# MCU.net
KiCad netlist of a schematic drawn in Altium Designer
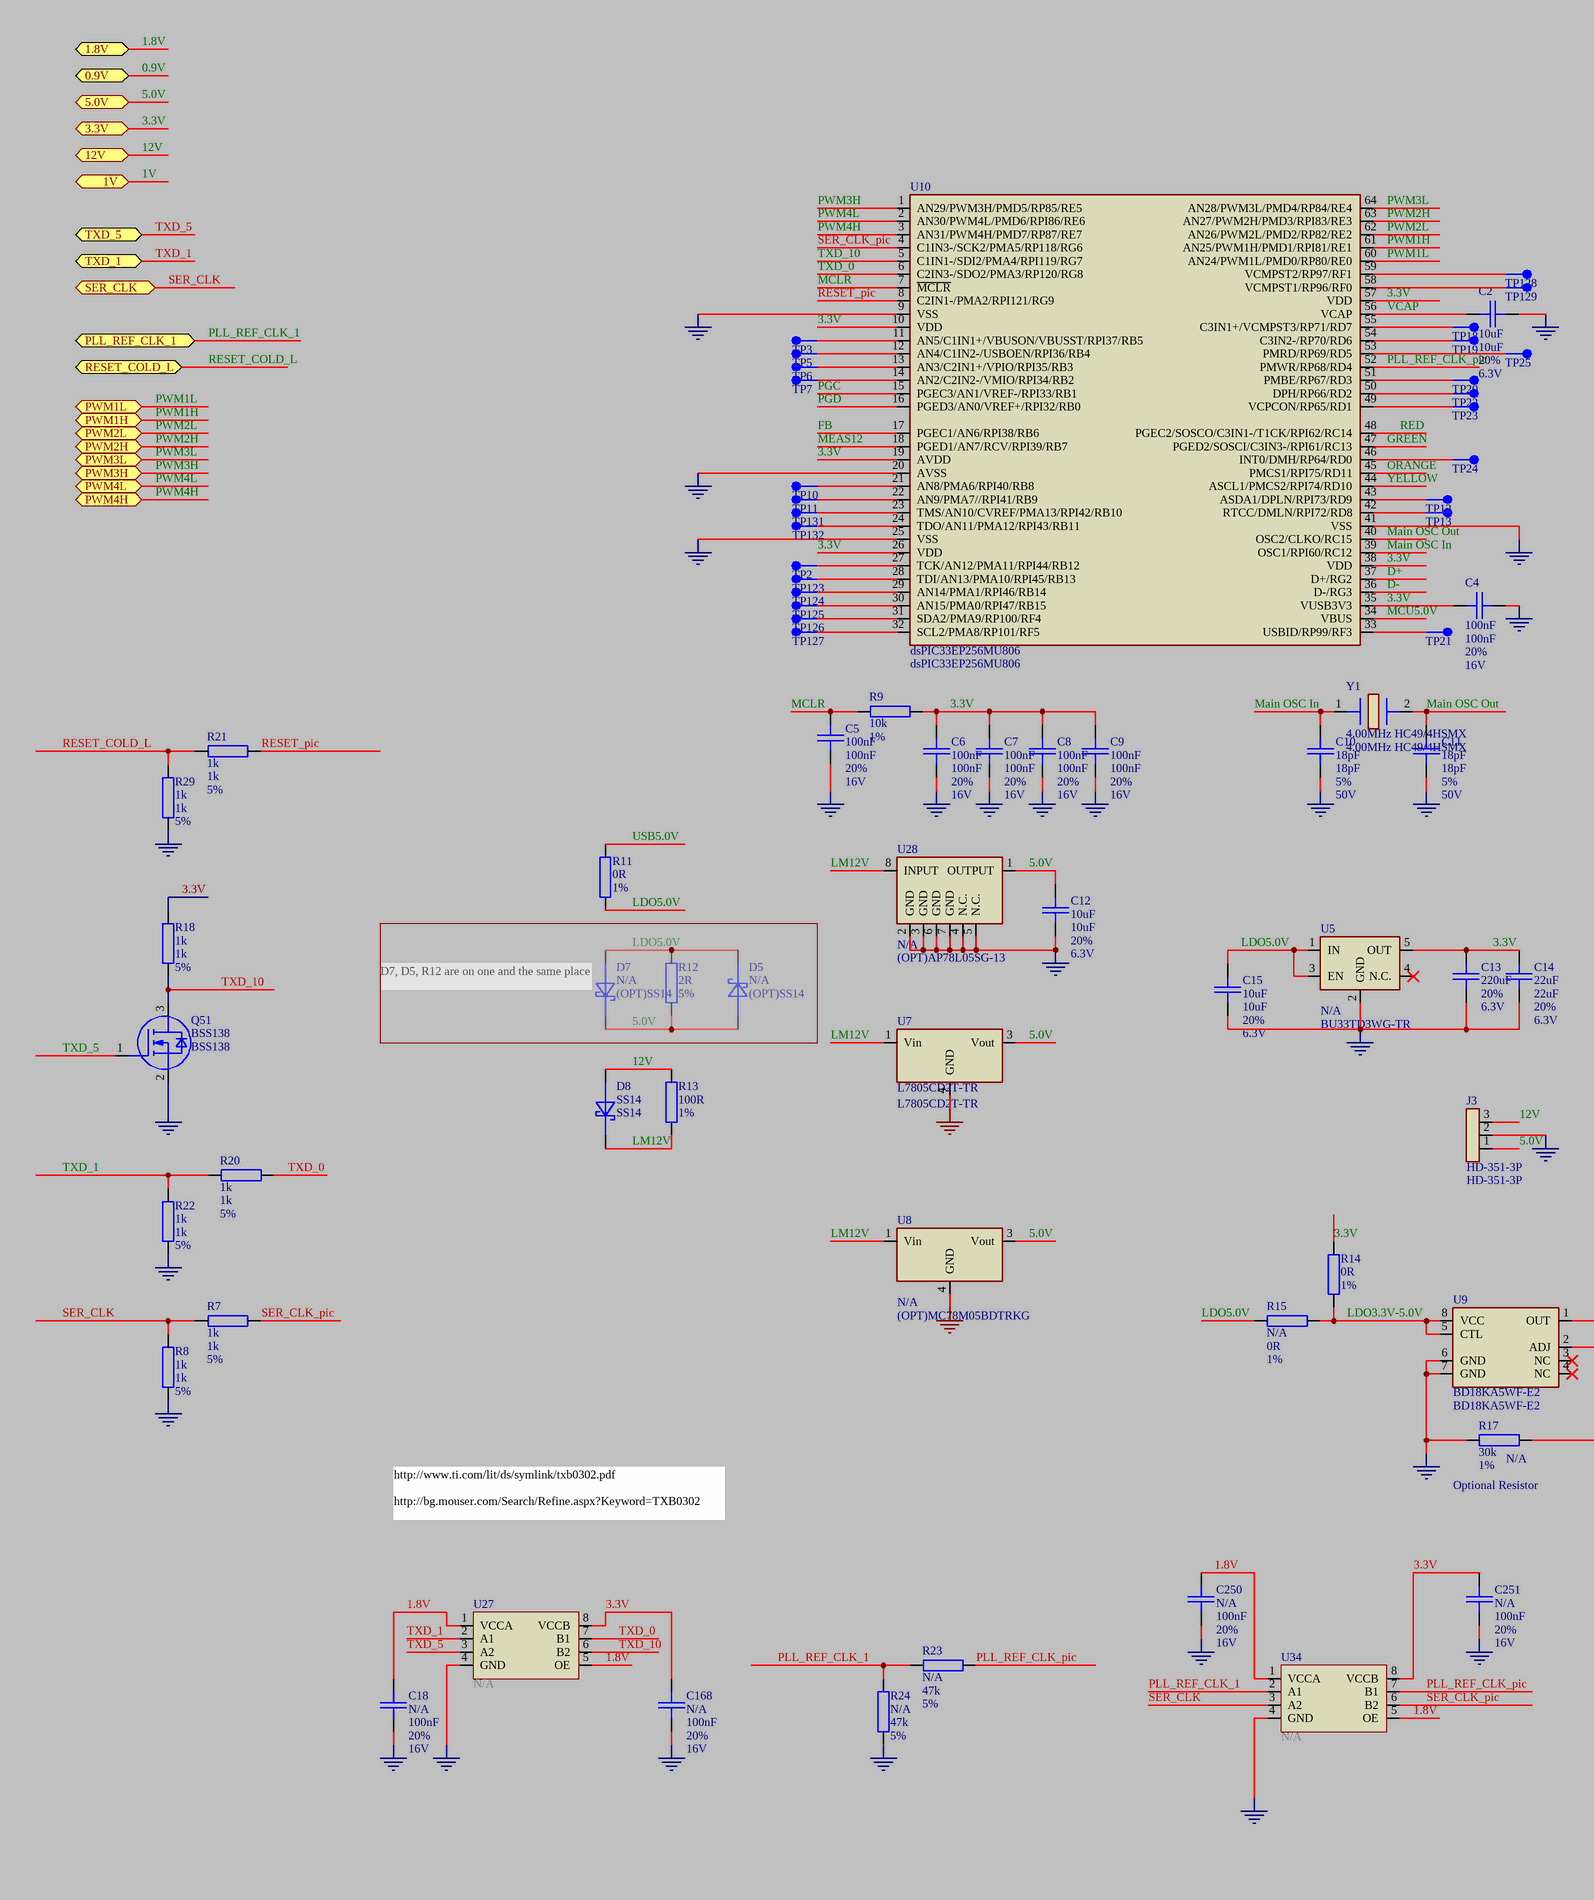
[diagram p0: MCU.SchDoc, left]
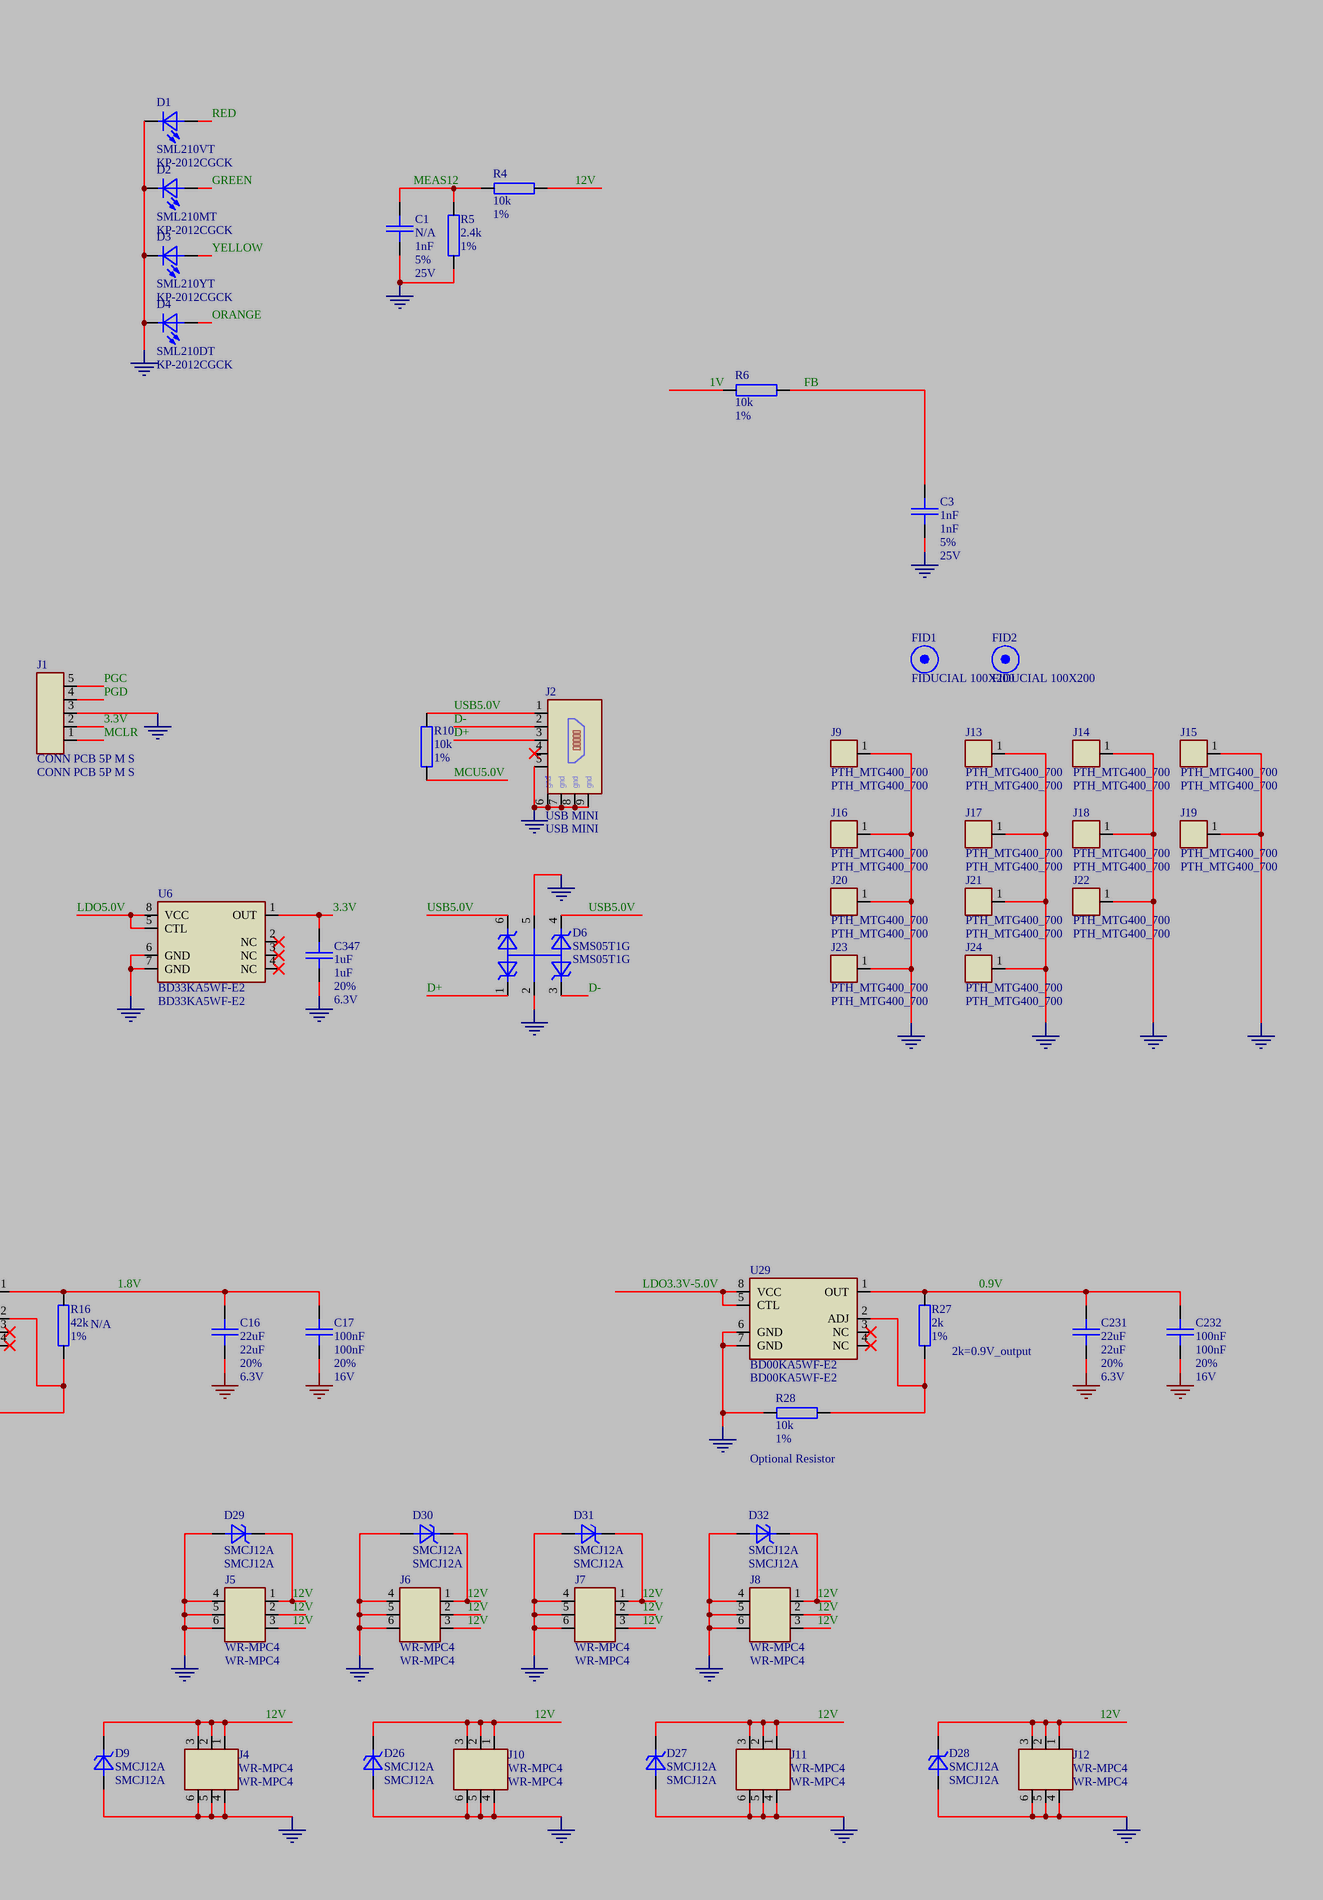
[diagram p1: MCU.SchDoc, right]

(export (version "E")
  (design (tool "Eeschema 10.0.6"))
  (components
    (comp (ref "C1")
      (value "N/A")
      (footprint "SMD_0603_CAPC1608X95N")
      (fields
        (field (name "DB_PART_NUMBER") "CAP000024113")
        (field (name "DB_VALUE") "1nF")
        (field (name "DB_TOLERANCE") "5%")
        (field (name "DB_VOLTAGE") "25V")
        (field (name "DB_MANUFACTURER_PART") "KEMET    C0603C102J3RAC")
      )
      (libsource (lib "") (part "=DB_VALUE_3"))
    )
    (comp (ref "C2")
      (value "10uF")
      (footprint "SMD_0603_CAPC1608X95N")
      (fields
        (field (name "DB_PART_NUMBER") "CAP000043646")
        (field (name "DB_VALUE") "10uF")
        (field (name "DB_TOLERANCE") "20%")
        (field (name "DB_VOLTAGE") "6.3V")
        (field (name "DB_MANUFACTURER_PART") "KEMET    C0603C106M9PAC")
      )
      (libsource (lib "") (part "=DB_VALUE_3"))
    )
    (comp (ref "C3")
      (value "1nF")
      (footprint "SMD_0603_CAPC1608X95N")
      (fields
        (field (name "DB_PART_NUMBER") "CAP000024113")
        (field (name "DB_VALUE") "1nF")
        (field (name "DB_TOLERANCE") "5%")
        (field (name "DB_VOLTAGE") "25V")
        (field (name "DB_MANUFACTURER_PART") "KEMET    C0603C102J3RAC")
      )
      (libsource (lib "") (part "=DB_VALUE_3"))
    )
    (comp (ref "C4")
      (value "100nF")
      (footprint "SMD_0402_CAPC1005X55N")
      (fields
        (field (name "DB_PART_NUMBER") "CAP000022751")
        (field (name "DB_VALUE") "100nF")
        (field (name "DB_TOLERANCE") "20%")
        (field (name "DB_VOLTAGE") "16V")
        (field (name "DB_MANUFACTURER_PART") "KEMET    C0402F104M4RAC")
      )
      (libsource (lib "") (part "=DB_VALUE_3"))
    )
    (comp (ref "C5")
      (value "100nF")
      (footprint "SMD_0402_CAPC1005X55N")
      (fields
        (field (name "DB_PART_NUMBER") "CAP000022751")
        (field (name "DB_VALUE") "100nF")
        (field (name "DB_TOLERANCE") "20%")
        (field (name "DB_VOLTAGE") "16V")
        (field (name "DB_MANUFACTURER_PART") "KEMET    C0402F104M4RAC")
      )
      (libsource (lib "") (part "=DB_VALUE_3"))
    )
    (comp (ref "C6")
      (value "100nF")
      (footprint "SMD_0402_CAPC1005X55N")
      (fields
        (field (name "DB_PART_NUMBER") "CAP000022751")
        (field (name "DB_VALUE") "100nF")
        (field (name "DB_TOLERANCE") "20%")
        (field (name "DB_VOLTAGE") "16V")
        (field (name "DB_MANUFACTURER_PART") "KEMET    C0402F104M4RAC")
      )
      (libsource (lib "") (part "=DB_VALUE_3"))
    )
    (comp (ref "C7")
      (value "100nF")
      (footprint "SMD_0402_CAPC1005X55N")
      (fields
        (field (name "DB_PART_NUMBER") "CAP000022751")
        (field (name "DB_VALUE") "100nF")
        (field (name "DB_TOLERANCE") "20%")
        (field (name "DB_VOLTAGE") "16V")
        (field (name "DB_MANUFACTURER_PART") "KEMET    C0402F104M4RAC")
      )
      (libsource (lib "") (part "=DB_VALUE_3"))
    )
    (comp (ref "C8")
      (value "100nF")
      (footprint "SMD_0402_CAPC1005X55N")
      (fields
        (field (name "DB_PART_NUMBER") "CAP000022751")
        (field (name "DB_VALUE") "100nF")
        (field (name "DB_TOLERANCE") "20%")
        (field (name "DB_VOLTAGE") "16V")
        (field (name "DB_MANUFACTURER_PART") "KEMET    C0402F104M4RAC")
      )
      (libsource (lib "") (part "=DB_VALUE_3"))
    )
    (comp (ref "C9")
      (value "100nF")
      (footprint "SMD_0402_CAPC1005X55N")
      (fields
        (field (name "DB_PART_NUMBER") "CAP000022751")
        (field (name "DB_VALUE") "100nF")
        (field (name "DB_TOLERANCE") "20%")
        (field (name "DB_VOLTAGE") "16V")
        (field (name "DB_MANUFACTURER_PART") "KEMET    C0402F104M4RAC")
      )
      (libsource (lib "") (part "=DB_VALUE_3"))
    )
    (comp (ref "C10")
      (value "18pF")
      (footprint "SMD_0603_CAPC1608X95N")
      (fields
        (field (name "DB_PART_NUMBER") "CAP000031922")
        (field (name "DB_VALUE") "18pF")
        (field (name "DB_TOLERANCE") "5%")
        (field (name "DB_VOLTAGE") "50V")
        (field (name "DB_MANUFACTURER_PART") "KEMET    C0603C180J5GAC")
      )
      (libsource (lib "") (part "=DB_VALUE_3"))
    )
    (comp (ref "C11")
      (value "18pF")
      (footprint "SMD_0603_CAPC1608X95N")
      (fields
        (field (name "DB_PART_NUMBER") "CAP000031922")
        (field (name "DB_VALUE") "18pF")
        (field (name "DB_TOLERANCE") "5%")
        (field (name "DB_VOLTAGE") "50V")
        (field (name "DB_MANUFACTURER_PART") "KEMET    C0603C180J5GAC")
      )
      (libsource (lib "") (part "=DB_VALUE_3"))
    )
    (comp (ref "C12")
      (value "10uF")
      (footprint "SMD_0603_CAPC1608X95N")
      (fields
        (field (name "DB_PART_NUMBER") "CAP000043646")
        (field (name "DB_VALUE") "10uF")
        (field (name "DB_TOLERANCE") "20%")
        (field (name "DB_VOLTAGE") "6.3V")
        (field (name "DB_MANUFACTURER_PART") "KEMET    C0603C106M9PAC")
      )
      (libsource (lib "") (part "=DB_VALUE_3"))
    )
    (comp (ref "C13")
      (value "220uF")
      (footprint "SMD_1210_CAPC3225X279N")
      (fields
        (field (name "DB_PART_NUMBER") "CAP000047355")
        (field (name "DB_VALUE") "220uF")
        (field (name "DB_TOLERANCE") "20%")
        (field (name "DB_VOLTAGE") "6.3V")
        (field (name "DB_MANUFACTURER_PART") "SAMSUNG    CL32A227MQVNNNE")
        (field (name "DB_APPROVED_BY") "VSN")
      )
      (libsource (lib "") (part "=DB_VALUE_3"))
    )
    (comp (ref "C14")
      (value "22uF")
      (footprint "SMD_0805_CAPC2012X145N")
      (fields
        (field (name "DB_PART_NUMBER") "CAP000043686")
        (field (name "DB_VALUE") "22uF")
        (field (name "DB_TOLERANCE") "20%")
        (field (name "DB_VOLTAGE") "6.3V")
        (field (name "DB_MANUFACTURER_PART") "KEMET    C0805C226M9PAC")
      )
      (libsource (lib "") (part "=DB_VALUE_3"))
    )
    (comp (ref "C15")
      (value "10uF")
      (footprint "SMD_0603_CAPC1608X95N")
      (fields
        (field (name "DB_PART_NUMBER") "CAP000043646")
        (field (name "DB_VALUE") "10uF")
        (field (name "DB_TOLERANCE") "20%")
        (field (name "DB_VOLTAGE") "6.3V")
        (field (name "DB_MANUFACTURER_PART") "KEMET    C0603C106M9PAC")
      )
      (libsource (lib "") (part "=DB_VALUE_3"))
    )
    (comp (ref "C16")
      (value "22uF")
      (footprint "SMD_0805_CAPC2012X145N")
      (fields
        (field (name "DB_PART_NUMBER") "CAP000043686")
        (field (name "DB_VALUE") "22uF")
        (field (name "DB_TOLERANCE") "20%")
        (field (name "DB_VOLTAGE") "6.3V")
        (field (name "DB_MANUFACTURER_PART") "KEMET    C0805C226M9PAC")
      )
      (libsource (lib "") (part "=DB_VALUE_3"))
    )
    (comp (ref "C17")
      (value "100nF")
      (footprint "SMD_0402_CAPC1005X55N")
      (fields
        (field (name "DB_PART_NUMBER") "CAP000022751")
        (field (name "DB_VALUE") "100nF")
        (field (name "DB_TOLERANCE") "20%")
        (field (name "DB_VOLTAGE") "16V")
        (field (name "DB_MANUFACTURER_PART") "KEMET    C0402F104M4RAC")
      )
      (libsource (lib "") (part "=DB_VALUE_3"))
    )
    (comp (ref "C18")
      (value "N/A")
      (footprint "SMD_0402_CAPC1005X55N")
      (fields
        (field (name "DB_PART_NUMBER") "CAP000022751")
        (field (name "DB_VALUE") "100nF")
        (field (name "DB_TOLERANCE") "20%")
        (field (name "DB_VOLTAGE") "16V")
        (field (name "DB_MANUFACTURER_PART") "KEMET    C0402F104M4RAC")
      )
      (libsource (lib "") (part "=DB_VALUE_3"))
    )
    (comp (ref "C168")
      (value "N/A")
      (footprint "SMD_0402_CAPC1005X55N")
      (fields
        (field (name "DB_PART_NUMBER") "CAP000022751")
        (field (name "DB_VALUE") "100nF")
        (field (name "DB_TOLERANCE") "20%")
        (field (name "DB_VOLTAGE") "16V")
        (field (name "DB_MANUFACTURER_PART") "KEMET    C0402F104M4RAC")
      )
      (libsource (lib "") (part "=DB_VALUE_3"))
    )
    (comp (ref "C231")
      (value "22uF")
      (footprint "SMD_0805_CAPC2012X145N")
      (fields
        (field (name "DB_PART_NUMBER") "CAP000043686")
        (field (name "DB_VALUE") "22uF")
        (field (name "DB_TOLERANCE") "20%")
        (field (name "DB_VOLTAGE") "6.3V")
        (field (name "DB_MANUFACTURER_PART") "KEMET    C0805C226M9PAC")
      )
      (libsource (lib "") (part "=DB_VALUE_3"))
    )
    (comp (ref "C232")
      (value "100nF")
      (footprint "SMD_0402_CAPC1005X55N")
      (fields
        (field (name "DB_PART_NUMBER") "CAP000022751")
        (field (name "DB_VALUE") "100nF")
        (field (name "DB_TOLERANCE") "20%")
        (field (name "DB_VOLTAGE") "16V")
        (field (name "DB_MANUFACTURER_PART") "KEMET    C0402F104M4RAC")
      )
      (libsource (lib "") (part "=DB_VALUE_3"))
    )
    (comp (ref "C250")
      (value "N/A")
      (footprint "SMD_0402_CAPC1005X55N")
      (fields
        (field (name "DB_PART_NUMBER") "CAP000022751")
        (field (name "DB_VALUE") "100nF")
        (field (name "DB_TOLERANCE") "20%")
        (field (name "DB_VOLTAGE") "16V")
        (field (name "DB_MANUFACTURER_PART") "KEMET    C0402F104M4RAC")
      )
      (libsource (lib "") (part "=DB_VALUE_3"))
    )
    (comp (ref "C251")
      (value "N/A")
      (footprint "SMD_0402_CAPC1005X55N")
      (fields
        (field (name "DB_PART_NUMBER") "CAP000022751")
        (field (name "DB_VALUE") "100nF")
        (field (name "DB_TOLERANCE") "20%")
        (field (name "DB_VOLTAGE") "16V")
        (field (name "DB_MANUFACTURER_PART") "KEMET    C0402F104M4RAC")
      )
      (libsource (lib "") (part "=DB_VALUE_3"))
    )
    (comp (ref "C347")
      (value "1uF")
      (footprint "SMD_0603_CAPC1608X95N")
      (fields
        (field (name "DB_PART_NUMBER") "CAP000043344")
        (field (name "DB_VALUE") "1uF")
        (field (name "DB_TOLERANCE") "20%")
        (field (name "DB_VOLTAGE") "6.3V")
        (field (name "DB_MANUFACTURER_PART") "KEMET    C0603C105M9PAC")
      )
      (libsource (lib "") (part "=DB_VALUE_3"))
    )
    (comp (ref "D1")
      (value "SML210VT")
      (footprint "SMD_0805_LED2012X100N")
      (fields
        (field (name "DB_PART_NUMBER") "OPT000000096")
        (field (name "DB_VALUE") "KP-2012CGCK")
        (field (name "DB_MANUFACTURER_PART") "KINGBRIGHT       KP-2012CGCK")
        (field (name "DB_APPROVED_BY") "VSN")
      )
      (libsource (lib "Database_Libs1") (part "LED"))
    )
    (comp (ref "D2")
      (value "SML210MT")
      (footprint "SMD_0805_LED2012X100N")
      (fields
        (field (name "DB_PART_NUMBER") "OPT000000096")
        (field (name "DB_VALUE") "KP-2012CGCK")
        (field (name "DB_MANUFACTURER_PART") "KINGBRIGHT       KP-2012CGCK")
        (field (name "DB_APPROVED_BY") "VSN")
      )
      (libsource (lib "Database_Libs1") (part "LED"))
    )
    (comp (ref "D3")
      (value "SML210YT")
      (footprint "SMD_0805_LED2012X100N")
      (fields
        (field (name "DB_PART_NUMBER") "OPT000000096")
        (field (name "DB_VALUE") "KP-2012CGCK")
        (field (name "DB_MANUFACTURER_PART") "KINGBRIGHT       KP-2012CGCK")
        (field (name "DB_APPROVED_BY") "VSN")
      )
      (libsource (lib "Database_Libs1") (part "LED"))
    )
    (comp (ref "D4")
      (value "SML210DT")
      (footprint "SMD_0805_LED2012X100N")
      (fields
        (field (name "DB_PART_NUMBER") "OPT000000096")
        (field (name "DB_VALUE") "KP-2012CGCK")
        (field (name "DB_MANUFACTURER_PART") "KINGBRIGHT       KP-2012CGCK")
        (field (name "DB_APPROVED_BY") "VSN")
      )
      (libsource (lib "Database_Libs1") (part "LED"))
    )
    (comp (ref "D5")
      (value "N/A")
      (footprint "SMD_DO214AC_SMA")
      (fields
        (field (name "DB_PART_NUMBER") "DDE000000580")
        (field (name "DB_VALUE") "(OPT)SS14")
        (field (name "DB_MANUFACTURER_PART") "Diodes        B140")
      )
      (libsource (lib "") (part "=DB_VALUE_13"))
    )
    (comp (ref "D6")
      (value "SMS05T1G")
      (footprint "SMD_SOT457_SOT95P275X110-6N")
      (fields
        (field (name "DB_PART_NUMBER") "DDE000002846")
        (field (name "DB_VALUE") "SMS05T1G")
        (field (name "DB_MANUFACTURER_PART") "ON SEMICONDUCTOR        SMS05T1G")
        (field (name "DB_APPROVED_BY") "VSN")
      )
      (libsource (lib "") (part "=DB_VALUE_15"))
    )
    (comp (ref "D7")
      (value "N/A")
      (footprint "SMD_DO214AC_SMA")
      (fields
        (field (name "DB_PART_NUMBER") "DDE000000580")
        (field (name "DB_VALUE") "(OPT)SS14")
        (field (name "DB_MANUFACTURER_PART") "Diodes        B140")
      )
      (libsource (lib "") (part "=DB_VALUE_13"))
    )
    (comp (ref "D8")
      (value "SS14")
      (footprint "SMD_DO214AC_SMA")
      (fields
        (field (name "DB_PART_NUMBER") "DDE000000580")
        (field (name "DB_VALUE") "SS14")
        (field (name "DB_MANUFACTURER_PART") "Diodes        B140")
      )
      (libsource (lib "") (part "=DB_VALUE_13"))
    )
    (comp (ref "D9")
      (value "SMCJ12A")
      (footprint "SMD_DO214AC_SMC")
      (fields
        (field (name "DB_PART_NUMBER") "DDE000001725")
        (field (name "DB_VALUE") "SMCJ12A")
        (field (name "DB_MANUFACTURER_PART") "Diodes        SMCJ12A")
      )
      (libsource (lib "") (part "=DB_VALUE_9"))
    )
    (comp (ref "D26")
      (value "SMCJ12A")
      (footprint "SMD_DO214AC_SMC")
      (fields
        (field (name "DB_PART_NUMBER") "DDE000001725")
        (field (name "DB_VALUE") "SMCJ12A")
        (field (name "DB_MANUFACTURER_PART") "Diodes        SMCJ12A")
      )
      (libsource (lib "") (part "=DB_VALUE_9"))
    )
    (comp (ref "D27")
      (value "SMCJ12A")
      (footprint "SMD_DO214AC_SMC")
      (fields
        (field (name "DB_PART_NUMBER") "DDE000001725")
        (field (name "DB_VALUE") "SMCJ12A")
        (field (name "DB_MANUFACTURER_PART") "Diodes        SMCJ12A")
      )
      (libsource (lib "") (part "=DB_VALUE_9"))
    )
    (comp (ref "D28")
      (value "SMCJ12A")
      (footprint "SMD_DO214AC_SMC")
      (fields
        (field (name "DB_PART_NUMBER") "DDE000001725")
        (field (name "DB_VALUE") "SMCJ12A")
        (field (name "DB_MANUFACTURER_PART") "Diodes        SMCJ12A")
      )
      (libsource (lib "") (part "=DB_VALUE_9"))
    )
    (comp (ref "D29")
      (value "SMCJ12A")
      (footprint "SMD_DO214AC_SMC")
      (fields
        (field (name "DB_PART_NUMBER") "DDE000001725")
        (field (name "DB_VALUE") "SMCJ12A")
        (field (name "DB_MANUFACTURER_PART") "Diodes        SMCJ12A")
      )
      (libsource (lib "") (part "=DB_VALUE_9"))
    )
    (comp (ref "D30")
      (value "SMCJ12A")
      (footprint "SMD_DO214AC_SMC")
      (fields
        (field (name "DB_PART_NUMBER") "DDE000001725")
        (field (name "DB_VALUE") "SMCJ12A")
        (field (name "DB_MANUFACTURER_PART") "Diodes        SMCJ12A")
      )
      (libsource (lib "") (part "=DB_VALUE_9"))
    )
    (comp (ref "D31")
      (value "SMCJ12A")
      (footprint "SMD_DO214AC_SMC")
      (fields
        (field (name "DB_PART_NUMBER") "DDE000001725")
        (field (name "DB_VALUE") "SMCJ12A")
        (field (name "DB_MANUFACTURER_PART") "Diodes        SMCJ12A")
      )
      (libsource (lib "") (part "=DB_VALUE_9"))
    )
    (comp (ref "D32")
      (value "SMCJ12A")
      (footprint "SMD_DO214AC_SMC")
      (fields
        (field (name "DB_PART_NUMBER") "DDE000001725")
        (field (name "DB_VALUE") "SMCJ12A")
        (field (name "DB_MANUFACTURER_PART") "Diodes        SMCJ12A")
      )
      (libsource (lib "") (part "=DB_VALUE_9"))
    )
    (comp (ref "FID1")
      (value "FIDUCIAL 100X200")
      (footprint "FID100X200")
      (fields
        (field (name "DB_PART_NUMBER") "FID000000001")
        (field (name "DB_MANUFACTURER_PART") "ISHIDDEN=T")
        (field (name "DB_APPROVED_BY") "ISHIDDEN=T")
      )
      (libsource (lib "") (part "=DB_VALUE_8"))
    )
    (comp (ref "FID2")
      (value "FIDUCIAL 100X200")
      (footprint "FID100X200")
      (fields
        (field (name "DB_PART_NUMBER") "FID000000001")
        (field (name "DB_MANUFACTURER_PART") "ISHIDDEN=T")
        (field (name "DB_APPROVED_BY") "ISHIDDEN=T")
      )
      (libsource (lib "") (part "=DB_VALUE_8"))
    )
    (comp (ref "J1")
      (value "CONN PCB 5P M S")
      (footprint "PTH_HDRV05W64P254_1X05")
      (fields
        (field (name "DB_PART_NUMBER") "CON000000006")
        (field (name "DB_VALUE") "CONN PCB 5P M S")
        (field (name "DB_MANUFACTURER_PART") "W+P        143-12-005-00")
        (field (name "DB_APPROVED_BY") "VSN")
      )
      (libsource (lib "") (part "=DB_VALUE_18"))
    )
    (comp (ref "J2")
      (value "USB MINI")
      (footprint "SMD_CON-CVILUX-CU04-SCM15B0")
      (fields
        (field (name "DB_PART_NUMBER") "CON000000048")
        (field (name "DB_VALUE") "USB MINI")
        (field (name "DB_MANUFACTURER_PART") "CVILUX       CU04-SCM15B0-R0-LF")
        (field (name "DB_APPROVED_BY") "VSN")
      )
      (libsource (lib "") (part "=DB_VALUE_16"))
    )
    (comp (ref "J3")
      (value "HD-351-3P")
      (footprint "PTH_CON_HD-351-3P")
      (fields
        (field (name "DB_PART_NUMBER") "CON000000272")
        (field (name "DB_VALUE") "HD-351-3P")
        (field (name "DB_MANUFACTURER_PART") "HOW DER      HD-351-3P")
        (field (name "DB_APPROVED_BY") "VSN")
      )
      (libsource (lib "") (part "=DB_VALUE_19"))
    )
    (comp (ref "J4")
      (value "WR-MPC4")
      (footprint "PTH_CON_WR-MRC4-6P_S")
      (fields
        (field (name "DB_PART_NUMBER") "CON000000279")
        (field (name "DB_VALUE") "WR-MPC4")
        (field (name "DB_MANUFACTURER_PART") "WE        	649 006 211 22")
        (field (name "DB_APPROVED_BY") "VSN")
      )
      (libsource (lib "") (part "=DB_VALUE_6"))
    )
    (comp (ref "J5")
      (value "WR-MPC4")
      (footprint "PTH_CON_WR-MRC4-6P_S")
      (fields
        (field (name "DB_PART_NUMBER") "CON000000279")
        (field (name "DB_VALUE") "WR-MPC4")
        (field (name "DB_MANUFACTURER_PART") "WE        	649 006 211 22")
        (field (name "DB_APPROVED_BY") "VSN")
      )
      (libsource (lib "") (part "=DB_VALUE_6"))
    )
    (comp (ref "J6")
      (value "WR-MPC4")
      (footprint "PTH_CON_WR-MRC4-6P_S")
      (fields
        (field (name "DB_PART_NUMBER") "CON000000279")
        (field (name "DB_VALUE") "WR-MPC4")
        (field (name "DB_MANUFACTURER_PART") "WE        	649 006 211 22")
        (field (name "DB_APPROVED_BY") "VSN")
      )
      (libsource (lib "") (part "=DB_VALUE_6"))
    )
    (comp (ref "J7")
      (value "WR-MPC4")
      (footprint "PTH_CON_WR-MRC4-6P_S")
      (fields
        (field (name "DB_PART_NUMBER") "CON000000279")
        (field (name "DB_VALUE") "WR-MPC4")
        (field (name "DB_MANUFACTURER_PART") "WE        	649 006 211 22")
        (field (name "DB_APPROVED_BY") "VSN")
      )
      (libsource (lib "") (part "=DB_VALUE_6"))
    )
    (comp (ref "J8")
      (value "WR-MPC4")
      (footprint "PTH_CON_WR-MRC4-6P_S")
      (fields
        (field (name "DB_PART_NUMBER") "CON000000279")
        (field (name "DB_VALUE") "WR-MPC4")
        (field (name "DB_MANUFACTURER_PART") "WE        	649 006 211 22")
        (field (name "DB_APPROVED_BY") "VSN")
      )
      (libsource (lib "") (part "=DB_VALUE_6"))
    )
    (comp (ref "J9")
      (value "PTH_MTG400_700")
      (footprint "PTH_MTG400_700")
      (fields
        (field (name "DB_PART_NUMBER") "MTH000000030")
        (field (name "DB_VALUE") "PTH_MTG400_700")
        (field (name "DB_APPROVED_BY") "VSN")
      )
      (libsource (lib "") (part "=DB_VALUE_4"))
    )
    (comp (ref "J10")
      (value "WR-MPC4")
      (footprint "PTH_CON_WR-MRC4-6P_S")
      (fields
        (field (name "DB_PART_NUMBER") "CON000000279")
        (field (name "DB_VALUE") "WR-MPC4")
        (field (name "DB_MANUFACTURER_PART") "WE        	649 006 211 22")
        (field (name "DB_APPROVED_BY") "VSN")
      )
      (libsource (lib "") (part "=DB_VALUE_6"))
    )
    (comp (ref "J11")
      (value "WR-MPC4")
      (footprint "PTH_CON_WR-MRC4-6P_S")
      (fields
        (field (name "DB_PART_NUMBER") "CON000000279")
        (field (name "DB_VALUE") "WR-MPC4")
        (field (name "DB_MANUFACTURER_PART") "WE        	649 006 211 22")
        (field (name "DB_APPROVED_BY") "VSN")
      )
      (libsource (lib "") (part "=DB_VALUE_6"))
    )
    (comp (ref "J12")
      (value "WR-MPC4")
      (footprint "PTH_CON_WR-MRC4-6P_S")
      (fields
        (field (name "DB_PART_NUMBER") "CON000000279")
        (field (name "DB_VALUE") "WR-MPC4")
        (field (name "DB_MANUFACTURER_PART") "WE        	649 006 211 22")
        (field (name "DB_APPROVED_BY") "VSN")
      )
      (libsource (lib "") (part "=DB_VALUE_6"))
    )
    (comp (ref "J13")
      (value "PTH_MTG400_700")
      (footprint "PTH_MTG400_700")
      (fields
        (field (name "DB_PART_NUMBER") "MTH000000030")
        (field (name "DB_VALUE") "PTH_MTG400_700")
        (field (name "DB_APPROVED_BY") "VSN")
      )
      (libsource (lib "") (part "=DB_VALUE_4"))
    )
    (comp (ref "J14")
      (value "PTH_MTG400_700")
      (footprint "PTH_MTG400_700")
      (fields
        (field (name "DB_PART_NUMBER") "MTH000000030")
        (field (name "DB_VALUE") "PTH_MTG400_700")
        (field (name "DB_APPROVED_BY") "VSN")
      )
      (libsource (lib "") (part "=DB_VALUE_4"))
    )
    (comp (ref "J15")
      (value "PTH_MTG400_700")
      (footprint "PTH_MTG400_700")
      (fields
        (field (name "DB_PART_NUMBER") "MTH000000030")
        (field (name "DB_VALUE") "PTH_MTG400_700")
        (field (name "DB_APPROVED_BY") "VSN")
      )
      (libsource (lib "") (part "=DB_VALUE_4"))
    )
    (comp (ref "J16")
      (value "PTH_MTG400_700")
      (footprint "PTH_MTG400_700")
      (fields
        (field (name "DB_PART_NUMBER") "MTH000000030")
        (field (name "DB_VALUE") "PTH_MTG400_700")
        (field (name "DB_APPROVED_BY") "VSN")
      )
      (libsource (lib "") (part "=DB_VALUE_4"))
    )
    (comp (ref "J17")
      (value "PTH_MTG400_700")
      (footprint "PTH_MTG400_700")
      (fields
        (field (name "DB_PART_NUMBER") "MTH000000030")
        (field (name "DB_VALUE") "PTH_MTG400_700")
        (field (name "DB_APPROVED_BY") "VSN")
      )
      (libsource (lib "") (part "=DB_VALUE_4"))
    )
    (comp (ref "J18")
      (value "PTH_MTG400_700")
      (footprint "PTH_MTG400_700")
      (fields
        (field (name "DB_PART_NUMBER") "MTH000000030")
        (field (name "DB_VALUE") "PTH_MTG400_700")
        (field (name "DB_APPROVED_BY") "VSN")
      )
      (libsource (lib "") (part "=DB_VALUE_4"))
    )
    (comp (ref "J19")
      (value "PTH_MTG400_700")
      (footprint "PTH_MTG400_700")
      (fields
        (field (name "DB_PART_NUMBER") "MTH000000030")
        (field (name "DB_VALUE") "PTH_MTG400_700")
        (field (name "DB_APPROVED_BY") "VSN")
      )
      (libsource (lib "") (part "=DB_VALUE_4"))
    )
    (comp (ref "J20")
      (value "PTH_MTG400_700")
      (footprint "PTH_MTG400_700")
      (fields
        (field (name "DB_PART_NUMBER") "MTH000000030")
        (field (name "DB_VALUE") "PTH_MTG400_700")
        (field (name "DB_APPROVED_BY") "VSN")
      )
      (libsource (lib "") (part "=DB_VALUE_4"))
    )
    (comp (ref "J21")
      (value "PTH_MTG400_700")
      (footprint "PTH_MTG400_700")
      (fields
        (field (name "DB_PART_NUMBER") "MTH000000030")
        (field (name "DB_VALUE") "PTH_MTG400_700")
        (field (name "DB_APPROVED_BY") "VSN")
      )
      (libsource (lib "") (part "=DB_VALUE_4"))
    )
    (comp (ref "J22")
      (value "PTH_MTG400_700")
      (footprint "PTH_MTG400_700")
      (fields
        (field (name "DB_PART_NUMBER") "MTH000000030")
        (field (name "DB_VALUE") "PTH_MTG400_700")
        (field (name "DB_APPROVED_BY") "VSN")
      )
      (libsource (lib "") (part "=DB_VALUE_4"))
    )
    (comp (ref "J23")
      (value "PTH_MTG400_700")
      (footprint "PTH_MTG400_700")
      (fields
        (field (name "DB_PART_NUMBER") "MTH000000030")
        (field (name "DB_VALUE") "PTH_MTG400_700")
        (field (name "DB_APPROVED_BY") "VSN")
      )
      (libsource (lib "") (part "=DB_VALUE_4"))
    )
    (comp (ref "J24")
      (value "PTH_MTG400_700")
      (footprint "PTH_MTG400_700")
      (fields
        (field (name "DB_PART_NUMBER") "MTH000000030")
        (field (name "DB_VALUE") "PTH_MTG400_700")
        (field (name "DB_APPROVED_BY") "VSN")
      )
      (libsource (lib "") (part "=DB_VALUE_4"))
    )
    (comp (ref "Q51")
      (value "BSS138")
      (footprint "SMD_SOT23_SOT95P240X112-3N")
      (fields
        (field (name "DB_PART_NUMBER") "TRA000001460")
        (field (name "DB_VALUE") "BSS138")
        (field (name "DB_MANUFACTURER_PART") "FAIRCHILD        BSS138LT1G")
        (field (name "DB_APPROVED_BY") "VSN")
      )
      (libsource (lib "") (part "=DB_VALUE_11"))
    )
    (comp (ref "R4")
      (value "N/A")
      (footprint "SMD_0603_RESC1608X55N")
      (fields
        (field (name "DB_PART_NUMBER") "RES000008663")
        (field (name "DB_VALUE") "10k")
        (field (name "DB_TOLERANCE") "1%")
        (field (name "DB_MANUFACTURER_PART") "YAGEO    RC0603FR-0710KL")
        (field (name "DB_APPROVED_BY") "VSN")
      )
      (libsource (lib "") (part "=DB_VALUE_2"))
    )
    (comp (ref "R5")
      (value "N/A")
      (footprint "SMD_0603_RESC1608X55N")
      (fields
        (field (name "DB_PART_NUMBER") "RES000006261")
        (field (name "DB_VALUE") "2.4k")
        (field (name "DB_TOLERANCE") "1%")
        (field (name "DB_MANUFACTURER_PART") "YAGEO    RC0603FR-072K4")
      )
      (libsource (lib "") (part "=DB_VALUE_2"))
    )
    (comp (ref "R6")
      (value "10k")
      (footprint "SMD_0603_RESC1608X55N")
      (fields
        (field (name "DB_PART_NUMBER") "RES000008663")
        (field (name "DB_VALUE") "10k")
        (field (name "DB_TOLERANCE") "1%")
        (field (name "DB_MANUFACTURER_PART") "YAGEO    RC0603FR-0710KL")
        (field (name "DB_APPROVED_BY") "VSN")
      )
      (libsource (lib "") (part "=DB_VALUE_2"))
    )
    (comp (ref "R7")
      (value "1k")
      (footprint "SMD_0603_RESC1608X55N")
      (fields
        (field (name "DB_PART_NUMBER") "RES000006462")
        (field (name "DB_VALUE") "1k")
        (field (name "DB_TOLERANCE") "5%")
        (field (name "DB_MANUFACTURER_PART") "YAGEO    RC0603JR-0747K")
      )
      (libsource (lib "") (part "=DB_VALUE_2"))
    )
    (comp (ref "R8")
      (value "1k")
      (footprint "SMD_0603_RESC1608X55N")
      (fields
        (field (name "DB_PART_NUMBER") "RES000006462")
        (field (name "DB_VALUE") "1k")
        (field (name "DB_TOLERANCE") "5%")
        (field (name "DB_MANUFACTURER_PART") "YAGEO    RC0603JR-0747K")
      )
      (libsource (lib "") (part "=DB_VALUE_2"))
    )
    (comp (ref "R9")
      (value "10k")
      (footprint "SMD_0603_RESC1608X55N")
      (fields
        (field (name "DB_PART_NUMBER") "RES000008663")
        (field (name "DB_VALUE") "10k")
        (field (name "DB_TOLERANCE") "1%")
        (field (name "DB_MANUFACTURER_PART") "YAGEO    RC0603FR-0710KL")
        (field (name "DB_APPROVED_BY") "VSN")
      )
      (libsource (lib "") (part "=DB_VALUE_2"))
    )
    (comp (ref "R10")
      (value "10k")
      (footprint "SMD_0603_RESC1608X55N")
      (fields
        (field (name "DB_PART_NUMBER") "RES000008663")
        (field (name "DB_VALUE") "10k")
        (field (name "DB_TOLERANCE") "1%")
        (field (name "DB_MANUFACTURER_PART") "YAGEO    RC0603FR-0710KL")
        (field (name "DB_APPROVED_BY") "VSN")
      )
      (libsource (lib "") (part "=DB_VALUE_2"))
    )
    (comp (ref "R11")
      (value "0R")
      (footprint "SMD_0603_RESC1608X55N")
      (fields
        (field (name "DB_PART_NUMBER") "RES000008926")
        (field (name "DB_VALUE") "0R")
        (field (name "DB_TOLERANCE") "1%")
        (field (name "DB_MANUFACTURER_PART") "YAGEO    AC0603FR-070RL")
        (field (name "DB_APPROVED_BY") "VSN")
      )
      (libsource (lib "") (part "=DB_VALUE_2"))
    )
    (comp (ref "R12")
      (value "2R")
      (footprint "SMD_1206_RESC3216X65N")
      (fields
        (field (name "DB_PART_NUMBER") "RES000007051")
        (field (name "DB_VALUE") "2R")
        (field (name "DB_TOLERANCE") "5%")
        (field (name "DB_MANUFACTURER_PART") "YAGEO    RC1206JR-072R")
      )
      (libsource (lib "") (part "=DB_VALUE_2"))
    )
    (comp (ref "R13")
      (value "100R")
      (footprint "SMD_1206_RESC3216X65N")
      (fields
        (field (name "DB_PART_NUMBER") "RES000006922")
        (field (name "DB_VALUE") "100R")
        (field (name "DB_TOLERANCE") "1%")
        (field (name "DB_MANUFACTURER_PART") "YAGEO    RC1206FR-07100R")
      )
      (libsource (lib "") (part "=DB_VALUE_2"))
    )
    (comp (ref "R14")
      (value "0R")
      (footprint "SMD_1206_RESC3216X65N")
      (fields
        (field (name "DB_PART_NUMBER") "RES000008756")
        (field (name "DB_VALUE") "0R")
        (field (name "DB_TOLERANCE") "1%")
        (field (name "DB_MANUFACTURER_PART") "YAGEO    AC1206FR-070RL")
        (field (name "DB_APPROVED_BY") "VSN")
      )
      (libsource (lib "") (part "=DB_VALUE_2"))
    )
    (comp (ref "R15")
      (value "N/A")
      (footprint "SMD_1206_RESC3216X65N")
      (fields
        (field (name "DB_PART_NUMBER") "RES000008756")
        (field (name "DB_VALUE") "0R")
        (field (name "DB_TOLERANCE") "1%")
        (field (name "DB_MANUFACTURER_PART") "YAGEO    AC1206FR-070RL")
        (field (name "DB_APPROVED_BY") "VSN")
      )
      (libsource (lib "") (part "=DB_VALUE_2"))
    )
    (comp (ref "R16")
      (value "N/A")
      (footprint "SMD_0603_RESC1608X55N")
      (fields
        (field (name "DB_PART_NUMBER") "RES000001590")
        (field (name "DB_VALUE") "42k")
        (field (name "DB_TOLERANCE") "1%")
        (field (name "DB_MANUFACTURER_PART") "YAGEO    RC0603FR-0741K2")
      )
      (libsource (lib "") (part "=DB_VALUE_2"))
    )
    (comp (ref "R17")
      (value "N/A")
      (footprint "SMD_0603_RESC1608X55N")
      (fields
        (field (name "DB_PART_NUMBER") "RES000006287")
        (field (name "DB_VALUE") "30k")
        (field (name "DB_TOLERANCE") "1%")
        (field (name "DB_MANUFACTURER_PART") "YAGEO    RC0603FR-0730K")
      )
      (libsource (lib "") (part "=DB_VALUE_2"))
    )
    (comp (ref "R18")
      (value "1k")
      (footprint "SMD_0603_RESC1608X55N")
      (fields
        (field (name "DB_PART_NUMBER") "RES000006462")
        (field (name "DB_VALUE") "1k")
        (field (name "DB_TOLERANCE") "5%")
        (field (name "DB_MANUFACTURER_PART") "YAGEO    RC0603JR-0747K")
      )
      (libsource (lib "") (part "=DB_VALUE_2"))
    )
    (comp (ref "R20")
      (value "1k")
      (footprint "SMD_0603_RESC1608X55N")
      (fields
        (field (name "DB_PART_NUMBER") "RES000006462")
        (field (name "DB_VALUE") "1k")
        (field (name "DB_TOLERANCE") "5%")
        (field (name "DB_MANUFACTURER_PART") "YAGEO    RC0603JR-0747K")
      )
      (libsource (lib "") (part "=DB_VALUE_2"))
    )
    (comp (ref "R21")
      (value "1k")
      (footprint "SMD_0603_RESC1608X55N")
      (fields
        (field (name "DB_PART_NUMBER") "RES000006462")
        (field (name "DB_VALUE") "1k")
        (field (name "DB_TOLERANCE") "5%")
        (field (name "DB_MANUFACTURER_PART") "YAGEO    RC0603JR-0747K")
      )
      (libsource (lib "") (part "=DB_VALUE_2"))
    )
    (comp (ref "R22")
      (value "1k")
      (footprint "SMD_0603_RESC1608X55N")
      (fields
        (field (name "DB_PART_NUMBER") "RES000006462")
        (field (name "DB_VALUE") "1k")
        (field (name "DB_TOLERANCE") "5%")
        (field (name "DB_MANUFACTURER_PART") "YAGEO    RC0603JR-0747K")
      )
      (libsource (lib "") (part "=DB_VALUE_2"))
    )
    (comp (ref "R23")
      (value "N/A")
      (footprint "SMD_0603_RESC1608X55N")
      (fields
        (field (name "DB_PART_NUMBER") "RES000006462")
        (field (name "DB_VALUE") "47k")
        (field (name "DB_TOLERANCE") "5%")
        (field (name "DB_MANUFACTURER_PART") "YAGEO    RC0603JR-0747K")
      )
      (libsource (lib "") (part "=DB_VALUE_2"))
    )
    (comp (ref "R24")
      (value "N/A")
      (footprint "SMD_0603_RESC1608X55N")
      (fields
        (field (name "DB_PART_NUMBER") "RES000006462")
        (field (name "DB_VALUE") "47k")
        (field (name "DB_TOLERANCE") "5%")
        (field (name "DB_MANUFACTURER_PART") "YAGEO    RC0603JR-0747K")
      )
      (libsource (lib "") (part "=DB_VALUE_2"))
    )
    (comp (ref "R27")
      (value "2k")
      (footprint "SMD_0603_RESC1608X55N")
      (fields
        (field (name "DB_PART_NUMBER") "RES000001590")
        (field (name "DB_VALUE") "2k")
        (field (name "DB_TOLERANCE") "1%")
        (field (name "DB_MANUFACTURER_PART") "YAGEO    RC0603FR-0741K2")
      )
      (libsource (lib "") (part "=DB_VALUE_2"))
    )
    (comp (ref "R28")
      (value "10k")
      (footprint "SMD_0603_RESC1608X55N")
      (fields
        (field (name "DB_PART_NUMBER") "RES000006287")
        (field (name "DB_VALUE") "10k")
        (field (name "DB_TOLERANCE") "1%")
        (field (name "DB_MANUFACTURER_PART") "YAGEO    RC0603FR-0730K")
      )
      (libsource (lib "") (part "=DB_VALUE_2"))
    )
    (comp (ref "R29")
      (value "1k")
      (footprint "SMD_0603_RESC1608X55N")
      (fields
        (field (name "DB_PART_NUMBER") "RES000006462")
        (field (name "DB_VALUE") "1k")
        (field (name "DB_TOLERANCE") "5%")
        (field (name "DB_MANUFACTURER_PART") "YAGEO    RC0603JR-0747K")
      )
      (libsource (lib "") (part "=DB_VALUE_2"))
    )
    (comp (ref "TP2")
      (value "100_254")
      (footprint "SMD_TP_100-254")
      (fields (field (name "DB_PART_NUMBER") "TPO000000001"))
      (libsource (lib "Database_Libs1") (part "=DB_VALUE"))
    )
    (comp (ref "TP3")
      (value "100_254")
      (footprint "SMD_TP_100-254")
      (fields (field (name "DB_PART_NUMBER") "TPO000000001"))
      (libsource (lib "Database_Libs1") (part "=DB_VALUE"))
    )
    (comp (ref "TP5")
      (value "100_254")
      (footprint "SMD_TP_100-254")
      (fields (field (name "DB_PART_NUMBER") "TPO000000001"))
      (libsource (lib "Database_Libs1") (part "=DB_VALUE"))
    )
    (comp (ref "TP6")
      (value "100_254")
      (footprint "SMD_TP_100-254")
      (fields (field (name "DB_PART_NUMBER") "TPO000000001"))
      (libsource (lib "Database_Libs1") (part "=DB_VALUE"))
    )
    (comp (ref "TP7")
      (value "100_254")
      (footprint "SMD_TP_100-254")
      (fields (field (name "DB_PART_NUMBER") "TPO000000001"))
      (libsource (lib "Database_Libs1") (part "=DB_VALUE"))
    )
    (comp (ref "TP10")
      (value "100_254")
      (footprint "SMD_TP_100-254")
      (fields (field (name "DB_PART_NUMBER") "TPO000000001"))
      (libsource (lib "Database_Libs1") (part "=DB_VALUE"))
    )
    (comp (ref "TP11")
      (value "100_254")
      (footprint "SMD_TP_100-254")
      (fields (field (name "DB_PART_NUMBER") "TPO000000001"))
      (libsource (lib "Database_Libs1") (part "=DB_VALUE"))
    )
    (comp (ref "TP12")
      (value "100_254")
      (footprint "SMD_TP_100-254")
      (fields (field (name "DB_PART_NUMBER") "TPO000000001"))
      (libsource (lib "Database_Libs1") (part "=DB_VALUE"))
    )
    (comp (ref "TP13")
      (value "100_254")
      (footprint "SMD_TP_100-254")
      (fields (field (name "DB_PART_NUMBER") "TPO000000001"))
      (libsource (lib "Database_Libs1") (part "=DB_VALUE"))
    )
    (comp (ref "TP18")
      (value "100_254")
      (footprint "SMD_TP_100-254")
      (fields (field (name "DB_PART_NUMBER") "TPO000000001"))
      (libsource (lib "Database_Libs1") (part "=DB_VALUE"))
    )
    (comp (ref "TP19")
      (value "100_254")
      (footprint "SMD_TP_100-254")
      (fields (field (name "DB_PART_NUMBER") "TPO000000001"))
      (libsource (lib "Database_Libs1") (part "=DB_VALUE"))
    )
    (comp (ref "TP20")
      (value "100_254")
      (footprint "SMD_TP_100-254")
      (fields (field (name "DB_PART_NUMBER") "TPO000000001"))
      (libsource (lib "Database_Libs1") (part "=DB_VALUE"))
    )
    (comp (ref "TP21")
      (value "100_254")
      (footprint "SMD_TP_100-254")
      (fields (field (name "DB_PART_NUMBER") "TPO000000001"))
      (libsource (lib "Database_Libs1") (part "=DB_VALUE"))
    )
    (comp (ref "TP22")
      (value "100_254")
      (footprint "SMD_TP_100-254")
      (fields (field (name "DB_PART_NUMBER") "TPO000000001"))
      (libsource (lib "Database_Libs1") (part "=DB_VALUE"))
    )
    (comp (ref "TP23")
      (value "100_254")
      (footprint "SMD_TP_100-254")
      (fields (field (name "DB_PART_NUMBER") "TPO000000001"))
      (libsource (lib "Database_Libs1") (part "=DB_VALUE"))
    )
    (comp (ref "TP24")
      (value "100_254")
      (footprint "SMD_TP_100-254")
      (fields (field (name "DB_PART_NUMBER") "TPO000000001"))
      (libsource (lib "Database_Libs1") (part "=DB_VALUE"))
    )
    (comp (ref "TP25")
      (value "100_254")
      (footprint "SMD_TP_100-254")
      (fields (field (name "DB_PART_NUMBER") "TPO000000001"))
      (libsource (lib "Database_Libs1") (part "=DB_VALUE"))
    )
    (comp (ref "TP123")
      (value "100_254")
      (footprint "SMD_TP_100-254")
      (fields (field (name "DB_PART_NUMBER") "TPO000000001"))
      (libsource (lib "Database_Libs1") (part "=DB_VALUE"))
    )
    (comp (ref "TP124")
      (value "100_254")
      (footprint "SMD_TP_100-254")
      (fields (field (name "DB_PART_NUMBER") "TPO000000001"))
      (libsource (lib "Database_Libs1") (part "=DB_VALUE"))
    )
    (comp (ref "TP125")
      (value "100_254")
      (footprint "SMD_TP_100-254")
      (fields (field (name "DB_PART_NUMBER") "TPO000000001"))
      (libsource (lib "Database_Libs1") (part "=DB_VALUE"))
    )
    (comp (ref "TP126")
      (value "100_254")
      (footprint "SMD_TP_100-254")
      (fields (field (name "DB_PART_NUMBER") "TPO000000001"))
      (libsource (lib "Database_Libs1") (part "=DB_VALUE"))
    )
    (comp (ref "TP127")
      (value "100_254")
      (footprint "SMD_TP_100-254")
      (fields (field (name "DB_PART_NUMBER") "TPO000000001"))
      (libsource (lib "Database_Libs1") (part "=DB_VALUE"))
    )
    (comp (ref "TP128")
      (value "100_254")
      (footprint "SMD_TP_100-254")
      (fields (field (name "DB_PART_NUMBER") "TPO000000001"))
      (libsource (lib "Database_Libs1") (part "=DB_VALUE"))
    )
    (comp (ref "TP129")
      (value "100_254")
      (footprint "SMD_TP_100-254")
      (fields (field (name "DB_PART_NUMBER") "TPO000000001"))
      (libsource (lib "Database_Libs1") (part "=DB_VALUE"))
    )
    (comp (ref "TP131")
      (value "100_254")
      (footprint "SMD_TP_100-254")
      (fields (field (name "DB_PART_NUMBER") "TPO000000001"))
      (libsource (lib "Database_Libs1") (part "=DB_VALUE"))
    )
    (comp (ref "TP132")
      (value "100_254")
      (footprint "SMD_TP_100-254")
      (fields (field (name "DB_PART_NUMBER") "TPO000000001"))
      (libsource (lib "Database_Libs1") (part "=DB_VALUE"))
    )
    (comp (ref "U5")
      (value "N/A")
      (footprint "SMD_SOT95P280X135-5N")
      (fields
        (field (name "DB_PART_NUMBER") "PSU000000126")
        (field (name "DB_VALUE") "BU33TD3WG-TR")
        (field (name "DB_MANUFACTURER_PART") "ROHM     BU33TD3WG-TR")
        (field (name "DB_APPROVED_BY") "VSN")
      )
      (libsource (lib "") (part "=DB_VALUE_14"))
    )
    (comp (ref "U6")
      (value "BD33KA5WF-E2")
      (footprint "SMD_SOIC127P620X160-8N")
      (fields
        (field (name "DB_PART_NUMBER") "PSU000000127")
        (field (name "DB_VALUE") "BD33KA5WF-E2")
        (field (name "DB_MANUFACTURER_PART") "ROHM        BD33KA5WF-E2")
        (field (name "DB_APPROVED_BY") "VSN")
      )
      (libsource (lib "") (part "=DB_VALUE_5"))
    )
    (comp (ref "U7")
      (value "L7805CD2T-TR")
      (footprint "SMD_TO254P1542X460-3_4N")
      (fields
        (field (name "DB_PART_NUMBER") "PSU000000129")
        (field (name "DB_VALUE") "L7805CD2T-TR")
        (field (name "DB_MANUFACTURER_PART") "ST       L7805CD2T-TR")
        (field (name "DB_APPROVED_BY") "VSN")
      )
      (libsource (lib "") (part "=DB_VALUE_7"))
    )
    (comp (ref "U8")
      (value "N/A")
      (footprint "SMD_TO229P991X239-4N_DPAK")
      (fields
        (field (name "DB_PART_NUMBER") "PSU000000031")
        (field (name "DB_VALUE") "(OPT)MC78M05BDTRKG")
        (field (name "DB_MANUFACTURER_PART") "ON Semiconductor       MC78M05BDTRKG")
        (field (name "DB_APPROVED_BY") "VSN")
      )
      (libsource (lib "") (part "=DB_VALUE_7"))
    )
    (comp (ref "U9")
      (value "BD18KA5WF-E2")
      (footprint "SMD_SOIC127P620X160-8N")
      (fields
        (field (name "DB_PART_NUMBER") "PSU000000128")
        (field (name "DB_VALUE") "BD18KA5WF-E2")
        (field (name "DB_MANUFACTURER_PART") "ROHM        BD00KA5WF-E2")
        (field (name "DB_APPROVED_BY") "VSN")
      )
      (libsource (lib "") (part "=DB_VALUE_10"))
    )
    (comp (ref "U10")
      (value "dsPIC33EP256MU806")
      (footprint "SMD_QFP50P1200X1200X120-64N")
      (fields
        (field (name "DB_PART_NUMBER") "MCU000000070")
        (field (name "DB_VALUE") "dsPIC33EP256MU806")
        (field (name "DB_MANUFACTURER_PART") "MICROCHIP        DSPIC33EP256MU806-E/PT")
        (field (name "DB_APPROVED_BY") "VSN")
      )
      (libsource (lib "") (part "=DB_VALUE_17"))
    )
    (comp (ref "U27")
      (value "N/A")
      (footprint "SMD_PSON40P120X180X40-8N")
      (libsource (lib "Schlib1") (part "=DB_VALUE"))
    )
    (comp (ref "U28")
      (value "N/A")
      (footprint "SMD_SOIC127P600X175-8N")
      (fields
        (field (name "DB_PART_NUMBER") "PSU000000125")
        (field (name "DB_VALUE") "(OPT)AP78L05SG-13")
        (field (name "DB_MANUFACTURER_PART") "DIODES        AP78L05SG-13")
        (field (name "DB_APPROVED_BY") "VSN")
      )
      (libsource (lib "") (part "=DB_VALUE_1"))
    )
    (comp (ref "U29")
      (value "BD00KA5WF-E2")
      (footprint "SMD_SOIC127P620X160-8N")
      (fields
        (field (name "DB_PART_NUMBER") "PSU000000128")
        (field (name "DB_VALUE") "BD00KA5WF-E2")
        (field (name "DB_MANUFACTURER_PART") "ROHM        BD00KA5WF-E2")
        (field (name "DB_APPROVED_BY") "VSN")
      )
      (libsource (lib "") (part "=DB_VALUE_10"))
    )
    (comp (ref "U34")
      (value "N/A")
      (footprint "SMD_PSON40P120X180X40-8N")
      (libsource (lib "Schlib1") (part "=DB_VALUE"))
    )
    (comp (ref "Y1")
      (value "4.00MHz HC49/4HSMX")
      (footprint "SMD_HC49_XTAL1140X480X420N")
      (fields
        (field (name "DB_PART_NUMBER") "OSC000000012")
        (field (name "DB_VALUE") "4.00MHz HC49/4HSMX")
        (field (name "DB_MANUFACTURER_PART") "IQD       4.00MHz HC49/4HSMX")
        (field (name "DB_APPROVED_BY") "VSN")
      )
      (libsource (lib "") (part "=DB_VALUE_12"))
    )
  )
  (nets
    (net (code "1") (name "/0.9V") (class "Default")
      (node (ref "C231") (pin "1") (pinfunction "1_1") (pintype "passive"))
      (node (ref "C232") (pin "1") (pinfunction "1_1") (pintype "passive"))
      (node (ref "R27") (pin "1") (pinfunction "1_1") (pintype "passive"))
      (node (ref "U29") (pin "1") (pinfunction "OUT_1") (pintype "passive"))
    )
    (net (code "2") (name "/1.8V") (class "Default")
      (node (ref "C16") (pin "1") (pinfunction "1_1") (pintype "passive"))
      (node (ref "C17") (pin "1") (pinfunction "1_1") (pintype "passive"))
      (node (ref "C18") (pin "2") (pinfunction "2_2") (pintype "passive"))
      (node (ref "C250") (pin "2") (pinfunction "2_2") (pintype "passive"))
      (node (ref "R16") (pin "1") (pinfunction "1_1") (pintype "passive"))
      (node (ref "U27") (pin "1") (pinfunction "VCCA_1") (pintype "passive"))
      (node (ref "U27") (pin "5") (pinfunction "OE_5") (pintype "passive"))
      (node (ref "U34") (pin "1") (pinfunction "VCCA_1") (pintype "passive"))
      (node (ref "U34") (pin "5") (pinfunction "OE_5") (pintype "passive"))
      (node (ref "U9") (pin "1") (pinfunction "OUT_1") (pintype "passive"))
    )
    (net (code "3") (name "/1V") (class "Default")
      (node (ref "R6") (pin "2") (pinfunction "2_2") (pintype "passive"))
    )
    (net (code "4") (name "/3.3V") (class "Default")
      (node (ref "C13") (pin "2") (pinfunction "2_2") (pintype "passive"))
      (node (ref "C14") (pin "1") (pinfunction "1_1") (pintype "passive"))
      (node (ref "C168") (pin "2") (pinfunction "2_2") (pintype "passive"))
      (node (ref "C251") (pin "2") (pinfunction "2_2") (pintype "passive"))
      (node (ref "C347") (pin "1") (pinfunction "1_1") (pintype "passive"))
      (node (ref "C4") (pin "1") (pinfunction "1_1") (pintype "passive"))
      (node (ref "C6") (pin "1") (pinfunction "1_1") (pintype "passive"))
      (node (ref "C7") (pin "1") (pinfunction "1_1") (pintype "passive"))
      (node (ref "C8") (pin "1") (pinfunction "1_1") (pintype "passive"))
      (node (ref "C9") (pin "1") (pinfunction "1_1") (pintype "passive"))
      (node (ref "J1") (pin "2") (pinfunction "2_2") (pintype "passive"))
      (node (ref "R14") (pin "2") (pinfunction "2_2") (pintype "passive"))
      (node (ref "R18") (pin "1") (pinfunction "1_1") (pintype "passive"))
      (node (ref "R9") (pin "2") (pinfunction "2_2") (pintype "passive"))
      (node (ref "U10") (pin "10") (pinfunction "VDD_10") (pintype "passive"))
      (node (ref "U10") (pin "19") (pinfunction "AVDD_19") (pintype "passive"))
      (node (ref "U10") (pin "26") (pinfunction "VDD_26") (pintype "passive"))
      (node (ref "U10") (pin "35") (pinfunction "VUSB3V3_35") (pintype "passive"))
      (node (ref "U10") (pin "38") (pinfunction "VDD_38") (pintype "passive"))
      (node (ref "U10") (pin "57") (pinfunction "VDD_57") (pintype "passive"))
      (node (ref "U27") (pin "8") (pinfunction "VCCB_8") (pintype "passive"))
      (node (ref "U34") (pin "8") (pinfunction "VCCB_8") (pintype "passive"))
      (node (ref "U5") (pin "5") (pinfunction "OUT_5") (pintype "passive"))
      (node (ref "U6") (pin "1") (pinfunction "OUT_1") (pintype "passive"))
    )
    (net (code "5") (name "/5.0V") (class "Default")
      (node (ref "C12") (pin "1") (pinfunction "1_1") (pintype "passive"))
      (node (ref "D5") (pin "2") (pinfunction "A_2") (pintype "passive"))
      (node (ref "D7") (pin "1") (pinfunction "C_1") (pintype "passive"))
      (node (ref "J3") (pin "1") (pinfunction "1_1") (pintype "passive"))
      (node (ref "R12") (pin "1") (pinfunction "1_1") (pintype "passive"))
      (node (ref "U28") (pin "1") (pinfunction "OUTPUT_1") (pintype "passive"))
      (node (ref "U7") (pin "3") (pinfunction "Vout_3") (pintype "passive"))
      (node (ref "U8") (pin "3") (pinfunction "Vout_3") (pintype "passive"))
    )
    (net (code "6") (name "/12V") (class "Default")
      (node (ref "D26") (pin "1") (pinfunction "C_1") (pintype "passive"))
      (node (ref "D27") (pin "1") (pinfunction "C_1") (pintype "passive"))
      (node (ref "D28") (pin "1") (pinfunction "C_1") (pintype "passive"))
      (node (ref "D29") (pin "1") (pinfunction "C_1") (pintype "passive"))
      (node (ref "D30") (pin "1") (pinfunction "C_1") (pintype "passive"))
      (node (ref "D31") (pin "1") (pinfunction "C_1") (pintype "passive"))
      (node (ref "D32") (pin "1") (pinfunction "C_1") (pintype "passive"))
      (node (ref "D8") (pin "2") (pinfunction "A_2") (pintype "passive"))
      (node (ref "D9") (pin "1") (pinfunction "C_1") (pintype "passive"))
      (node (ref "J10") (pin "1") (pinfunction "1_1") (pintype "passive"))
      (node (ref "J10") (pin "2") (pinfunction "2_2") (pintype "passive"))
      (node (ref "J10") (pin "3") (pinfunction "3_3") (pintype "passive"))
      (node (ref "J11") (pin "1") (pinfunction "1_1") (pintype "passive"))
      (node (ref "J11") (pin "2") (pinfunction "2_2") (pintype "passive"))
      (node (ref "J11") (pin "3") (pinfunction "3_3") (pintype "passive"))
      (node (ref "J12") (pin "1") (pinfunction "1_1") (pintype "passive"))
      (node (ref "J12") (pin "2") (pinfunction "2_2") (pintype "passive"))
      (node (ref "J12") (pin "3") (pinfunction "3_3") (pintype "passive"))
      (node (ref "J3") (pin "3") (pinfunction "3_3") (pintype "passive"))
      (node (ref "J4") (pin "1") (pinfunction "1_1") (pintype "passive"))
      (node (ref "J4") (pin "2") (pinfunction "2_2") (pintype "passive"))
      (node (ref "J4") (pin "3") (pinfunction "3_3") (pintype "passive"))
      (node (ref "J5") (pin "1") (pinfunction "1_1") (pintype "passive"))
      (node (ref "J5") (pin "2") (pinfunction "2_2") (pintype "passive"))
      (node (ref "J5") (pin "3") (pinfunction "3_3") (pintype "passive"))
      (node (ref "J6") (pin "1") (pinfunction "1_1") (pintype "passive"))
      (node (ref "J6") (pin "2") (pinfunction "2_2") (pintype "passive"))
      (node (ref "J6") (pin "3") (pinfunction "3_3") (pintype "passive"))
      (node (ref "J7") (pin "1") (pinfunction "1_1") (pintype "passive"))
      (node (ref "J7") (pin "2") (pinfunction "2_2") (pintype "passive"))
      (node (ref "J7") (pin "3") (pinfunction "3_3") (pintype "passive"))
      (node (ref "J8") (pin "1") (pinfunction "1_1") (pintype "passive"))
      (node (ref "J8") (pin "2") (pinfunction "2_2") (pintype "passive"))
      (node (ref "J8") (pin "3") (pinfunction "3_3") (pintype "passive"))
      (node (ref "R13") (pin "2") (pinfunction "2_2") (pintype "passive"))
      (node (ref "R4") (pin "1") (pinfunction "1_1") (pintype "passive"))
    )
    (net (code "7") (name "/D+") (class "Default")
      (node (ref "D6") (pin "1") (pinfunction "1_1") (pintype "passive"))
      (node (ref "J2") (pin "3") (pinfunction "3_3") (pintype "passive"))
      (node (ref "U10") (pin "37") (pinfunction "D+/RG2_37") (pintype "passive"))
    )
    (net (code "8") (name "/D-") (class "Default")
      (node (ref "D6") (pin "3") (pinfunction "3_3") (pintype "passive"))
      (node (ref "J2") (pin "2") (pinfunction "2_2") (pintype "passive"))
      (node (ref "U10") (pin "36") (pinfunction "D-/RG3_36") (pintype "passive"))
    )
    (net (code "9") (name "/FB") (class "Default")
      (node (ref "C3") (pin "1") (pinfunction "1_1") (pintype "passive"))
      (node (ref "R6") (pin "1") (pinfunction "1_1") (pintype "passive"))
      (node (ref "U10") (pin "17") (pinfunction "PGEC1/AN6/RPI38/RB6_17") (pintype "passive"))
    )
    (net (code "10") (name "/GREEN") (class "Default")
      (node (ref "D2") (pin "2") (pinfunction "A_2") (pintype "passive"))
      (node (ref "U10") (pin "47") (pinfunction "PGED2/SOSCI/C3IN3-/RPI61/RC13_47") (pintype "passive"))
    )
    (net (code "11") (name "/LDO3.3V-5.0V") (class "Default")
      (node (ref "R14") (pin "1") (pinfunction "1_1") (pintype "passive"))
      (node (ref "R15") (pin "1") (pinfunction "1_1") (pintype "passive"))
      (node (ref "U29") (pin "5") (pinfunction "CTL_5") (pintype "passive"))
      (node (ref "U29") (pin "8") (pinfunction "VCC_8") (pintype "passive"))
      (node (ref "U9") (pin "5") (pinfunction "CTL_5") (pintype "passive"))
      (node (ref "U9") (pin "8") (pinfunction "VCC_8") (pintype "passive"))
    )
    (net (code "12") (name "/LDO5.0V") (class "Default")
      (node (ref "C15") (pin "1") (pinfunction "1_1") (pintype "passive"))
      (node (ref "D5") (pin "1") (pinfunction "C_1") (pintype "passive"))
      (node (ref "D7") (pin "2") (pinfunction "A_2") (pintype "passive"))
      (node (ref "R11") (pin "1") (pinfunction "1_1") (pintype "passive"))
      (node (ref "R12") (pin "2") (pinfunction "2_2") (pintype "passive"))
      (node (ref "R15") (pin "2") (pinfunction "2_2") (pintype "passive"))
      (node (ref "U5") (pin "1") (pinfunction "IN_1") (pintype "passive"))
      (node (ref "U5") (pin "3") (pinfunction "EN_3") (pintype "passive"))
      (node (ref "U6") (pin "5") (pinfunction "CTL_5") (pintype "passive"))
      (node (ref "U6") (pin "8") (pinfunction "VCC_8") (pintype "passive"))
    )
    (net (code "13") (name "/LM12V") (class "Default")
      (node (ref "D8") (pin "1") (pinfunction "C_1") (pintype "passive"))
      (node (ref "R13") (pin "1") (pinfunction "1_1") (pintype "passive"))
      (node (ref "U28") (pin "8") (pinfunction "INPUT_8") (pintype "passive"))
      (node (ref "U7") (pin "1") (pinfunction "Vin_1") (pintype "passive"))
      (node (ref "U8") (pin "1") (pinfunction "Vin_1") (pintype "passive"))
    )
    (net (code "14") (name "/MCLR") (class "Default")
      (node (ref "C5") (pin "1") (pinfunction "1_1") (pintype "passive"))
      (node (ref "J1") (pin "1") (pinfunction "1_1") (pintype "passive"))
      (node (ref "R9") (pin "1") (pinfunction "1_1") (pintype "passive"))
      (node (ref "U10") (pin "7") (pinfunction "~{MCLR}_7") (pintype "passive"))
    )
    (net (code "15") (name "/MCU5.0V") (class "Default")
      (node (ref "R10") (pin "2") (pinfunction "2_2") (pintype "passive"))
      (node (ref "U10") (pin "34") (pinfunction "VBUS_34") (pintype "passive"))
    )
    (net (code "16") (name "/MEAS12") (class "Default")
      (node (ref "C1") (pin "1") (pinfunction "1_1") (pintype "passive"))
      (node (ref "R4") (pin "2") (pinfunction "2_2") (pintype "passive"))
      (node (ref "R5") (pin "2") (pinfunction "2_2") (pintype "passive"))
      (node (ref "U10") (pin "18") (pinfunction "PGED1/AN7/RCV/RPI39/RB7_18") (pintype "passive"))
    )
    (net (code "17") (name "/Main OSC In") (class "Default")
      (node (ref "C10") (pin "1") (pinfunction "1_1") (pintype "passive"))
      (node (ref "U10") (pin "39") (pinfunction "OSC1/RPI60/RC12_39") (pintype "passive"))
      (node (ref "Y1") (pin "1") (pinfunction "1_1") (pintype "passive"))
    )
    (net (code "18") (name "/Main OSC Out") (class "Default")
      (node (ref "C11") (pin "1") (pinfunction "1_1") (pintype "passive"))
      (node (ref "U10") (pin "40") (pinfunction "OSC2/CLKO/RC15_40") (pintype "passive"))
      (node (ref "Y1") (pin "2") (pinfunction "2_2") (pintype "passive"))
    )
    (net (code "19") (name "/ORANGE") (class "Default")
      (node (ref "D4") (pin "2") (pinfunction "A_2") (pintype "passive"))
      (node (ref "U10") (pin "45") (pinfunction "PMCS1/RPI75/RD11_45") (pintype "passive"))
    )
    (net (code "20") (name "/PGC") (class "Default")
      (node (ref "J1") (pin "5") (pinfunction "5_5") (pintype "passive"))
      (node (ref "U10") (pin "15") (pinfunction "PGEC3/AN1/VREF-/RPI33/RB1_15") (pintype "passive"))
    )
    (net (code "21") (name "/PGD") (class "Default")
      (node (ref "J1") (pin "4") (pinfunction "4_4") (pintype "passive"))
      (node (ref "U10") (pin "16") (pinfunction "PGED3/AN0/VREF+/RPI32/RB0_16") (pintype "passive"))
    )
    (net (code "22") (name "/PLL_REF_CLK_1") (class "Default")
      (node (ref "R23") (pin "1") (pinfunction "1_1") (pintype "passive"))
      (node (ref "R24") (pin "1") (pinfunction "1_1") (pintype "passive"))
      (node (ref "U34") (pin "2") (pinfunction "A1_2") (pintype "passive"))
    )
    (net (code "23") (name "/PLL_REF_CLK_pic") (class "Default")
      (node (ref "R23") (pin "2") (pinfunction "2_2") (pintype "passive"))
      (node (ref "U10") (pin "52") (pinfunction "PMWR/RP68/RD4_52") (pintype "passive"))
      (node (ref "U34") (pin "7") (pinfunction "B1_7") (pintype "passive"))
    )
    (net (code "24") (name "/PWM1H") (class "Default")
      (node (ref "U10") (pin "61") (pinfunction "AN25/PWM1H/PMD1/RPI81/RE1_61") (pintype "passive"))
    )
    (net (code "25") (name "/PWM1L") (class "Default")
      (node (ref "U10") (pin "60") (pinfunction "AN24/PWM1L/PMD0/RP80/RE0_60") (pintype "passive"))
    )
    (net (code "26") (name "/PWM2H") (class "Default")
      (node (ref "U10") (pin "63") (pinfunction "AN27/PWM2H/PMD3/RPI83/RE3_63") (pintype "passive"))
    )
    (net (code "27") (name "/PWM2L") (class "Default")
      (node (ref "U10") (pin "62") (pinfunction "AN26/PWM2L/PMD2/RP82/RE2_62") (pintype "passive"))
    )
    (net (code "28") (name "/PWM3H") (class "Default")
      (node (ref "U10") (pin "1") (pinfunction "AN29/PWM3H/PMD5/RP85/RE5_1") (pintype "passive"))
    )
    (net (code "29") (name "/PWM3L") (class "Default")
      (node (ref "U10") (pin "64") (pinfunction "AN28/PWM3L/PMD4/RP84/RE4_64") (pintype "passive"))
    )
    (net (code "30") (name "/PWM4H") (class "Default")
      (node (ref "U10") (pin "3") (pinfunction "AN31/PWM4H/PMD7/RP87/RE7_3") (pintype "passive"))
    )
    (net (code "31") (name "/PWM4L") (class "Default")
      (node (ref "U10") (pin "2") (pinfunction "AN30/PWM4L/PMD6/RPI86/RE6_2") (pintype "passive"))
    )
    (net (code "32") (name "/RED") (class "Default")
      (node (ref "D1") (pin "2") (pinfunction "A_2") (pintype "passive"))
      (node (ref "U10") (pin "48") (pinfunction "PGEC2/SOSCO/C3IN1-/T1CK/RPI62/RC14_48") (pintype "passive"))
    )
    (net (code "33") (name "/RESET_COLD_L") (class "Default")
      (node (ref "R21") (pin "1") (pinfunction "1_1") (pintype "passive"))
      (node (ref "R29") (pin "1") (pinfunction "1_1") (pintype "passive"))
    )
    (net (code "34") (name "/RESET_pic") (class "Default")
      (node (ref "R21") (pin "2") (pinfunction "2_2") (pintype "passive"))
      (node (ref "U10") (pin "8") (pinfunction "C2IN1-/PMA2/RPI121/RG9_8") (pintype "passive"))
    )
    (net (code "35") (name "/SER_CLK") (class "Default")
      (node (ref "R7") (pin "1") (pinfunction "1_1") (pintype "passive"))
      (node (ref "R8") (pin "1") (pinfunction "1_1") (pintype "passive"))
      (node (ref "U34") (pin "3") (pinfunction "A2_3") (pintype "passive"))
    )
    (net (code "36") (name "/SER_CLK_pic") (class "Default")
      (node (ref "R7") (pin "2") (pinfunction "2_2") (pintype "passive"))
      (node (ref "U10") (pin "4") (pinfunction "C1IN3-/SCK2/PMA5/RP118/RG6_4") (pintype "passive"))
      (node (ref "U34") (pin "6") (pinfunction "B2_6") (pintype "passive"))
    )
    (net (code "37") (name "/TXD_0") (class "Default")
      (node (ref "R20") (pin "2") (pinfunction "2_2") (pintype "passive"))
      (node (ref "U10") (pin "6") (pinfunction "C2IN3-/SDO2/PMA3/RP120/RG8_6") (pintype "passive"))
      (node (ref "U27") (pin "7") (pinfunction "B1_7") (pintype "passive"))
    )
    (net (code "38") (name "/TXD_1") (class "Default")
      (node (ref "R20") (pin "1") (pinfunction "1_1") (pintype "passive"))
      (node (ref "R22") (pin "1") (pinfunction "1_1") (pintype "passive"))
      (node (ref "U27") (pin "2") (pinfunction "A1_2") (pintype "passive"))
    )
    (net (code "39") (name "/TXD_5") (class "Default")
      (node (ref "Q51") (pin "1") (pinfunction "G_1") (pintype "passive"))
      (node (ref "U27") (pin "3") (pinfunction "A2_3") (pintype "passive"))
    )
    (net (code "40") (name "/TXD_10") (class "Default")
      (node (ref "Q51") (pin "3") (pinfunction "D_3") (pintype "passive"))
      (node (ref "R18") (pin "2") (pinfunction "2_2") (pintype "passive"))
      (node (ref "U10") (pin "5") (pinfunction "C1IN1-/SDI2/PMA4/RPI119/RG7_5") (pintype "passive"))
      (node (ref "U27") (pin "6") (pinfunction "B2_6") (pintype "passive"))
    )
    (net (code "41") (name "/USB5.0V") (class "Default")
      (node (ref "D6") (pin "4") (pinfunction "4_4") (pintype "passive"))
      (node (ref "D6") (pin "6") (pinfunction "6_6") (pintype "passive"))
      (node (ref "J2") (pin "1") (pinfunction "1_1") (pintype "passive"))
      (node (ref "R10") (pin "1") (pinfunction "1_1") (pintype "passive"))
      (node (ref "R11") (pin "2") (pinfunction "2_2") (pintype "passive"))
    )
    (net (code "42") (name "/VCAP") (class "Default")
      (node (ref "C2") (pin "1") (pinfunction "1_1") (pintype "passive"))
      (node (ref "U10") (pin "56") (pinfunction "VCAP_56") (pintype "passive"))
    )
    (net (code "43") (name "/YELLOW") (class "Default")
      (node (ref "D3") (pin "2") (pinfunction "A_2") (pintype "passive"))
      (node (ref "U10") (pin "44") (pinfunction "ASCL1/PMCS2/RPI74/RD10_44") (pintype "passive"))
    )
    (net (code "44") (name "GND") (class "Default")
      (node (ref "C1") (pin "2") (pinfunction "2_2") (pintype "passive"))
      (node (ref "C10") (pin "2") (pinfunction "2_2") (pintype "passive"))
      (node (ref "C11") (pin "2") (pinfunction "2_2") (pintype "passive"))
      (node (ref "C12") (pin "2") (pinfunction "2_2") (pintype "passive"))
      (node (ref "C13") (pin "1") (pinfunction "1_1") (pintype "passive"))
      (node (ref "C14") (pin "2") (pinfunction "2_2") (pintype "passive"))
      (node (ref "C15") (pin "2") (pinfunction "2_2") (pintype "passive"))
      (node (ref "C16") (pin "2") (pinfunction "2_2") (pintype "passive"))
      (node (ref "C168") (pin "1") (pinfunction "1_1") (pintype "passive"))
      (node (ref "C17") (pin "2") (pinfunction "2_2") (pintype "passive"))
      (node (ref "C18") (pin "1") (pinfunction "1_1") (pintype "passive"))
      (node (ref "C2") (pin "2") (pinfunction "2_2") (pintype "passive"))
      (node (ref "C231") (pin "2") (pinfunction "2_2") (pintype "passive"))
      (node (ref "C232") (pin "2") (pinfunction "2_2") (pintype "passive"))
      (node (ref "C250") (pin "1") (pinfunction "1_1") (pintype "passive"))
      (node (ref "C251") (pin "1") (pinfunction "1_1") (pintype "passive"))
      (node (ref "C3") (pin "2") (pinfunction "2_2") (pintype "passive"))
      (node (ref "C347") (pin "2") (pinfunction "2_2") (pintype "passive"))
      (node (ref "C4") (pin "2") (pinfunction "2_2") (pintype "passive"))
      (node (ref "C5") (pin "2") (pinfunction "2_2") (pintype "passive"))
      (node (ref "C6") (pin "2") (pinfunction "2_2") (pintype "passive"))
      (node (ref "C7") (pin "2") (pinfunction "2_2") (pintype "passive"))
      (node (ref "C8") (pin "2") (pinfunction "2_2") (pintype "passive"))
      (node (ref "C9") (pin "2") (pinfunction "2_2") (pintype "passive"))
      (node (ref "D1") (pin "1") (pinfunction "C_1") (pintype "passive"))
      (node (ref "D2") (pin "1") (pinfunction "C_1") (pintype "passive"))
      (node (ref "D26") (pin "2") (pinfunction "A_2") (pintype "passive"))
      (node (ref "D27") (pin "2") (pinfunction "A_2") (pintype "passive"))
      (node (ref "D28") (pin "2") (pinfunction "A_2") (pintype "passive"))
      (node (ref "D29") (pin "2") (pinfunction "A_2") (pintype "passive"))
      (node (ref "D3") (pin "1") (pinfunction "C_1") (pintype "passive"))
      (node (ref "D30") (pin "2") (pinfunction "A_2") (pintype "passive"))
      (node (ref "D31") (pin "2") (pinfunction "A_2") (pintype "passive"))
      (node (ref "D32") (pin "2") (pinfunction "A_2") (pintype "passive"))
      (node (ref "D4") (pin "1") (pinfunction "C_1") (pintype "passive"))
      (node (ref "D6") (pin "2") (pinfunction "2_2") (pintype "passive"))
      (node (ref "D6") (pin "5") (pinfunction "5_5") (pintype "passive"))
      (node (ref "D9") (pin "2") (pinfunction "A_2") (pintype "passive"))
      (node (ref "J1") (pin "3") (pinfunction "3_3") (pintype "passive"))
      (node (ref "J10") (pin "4") (pinfunction "4_4") (pintype "passive"))
      (node (ref "J10") (pin "5") (pinfunction "5_5") (pintype "passive"))
      (node (ref "J10") (pin "6") (pinfunction "6_6") (pintype "passive"))
      (node (ref "J11") (pin "4") (pinfunction "4_4") (pintype "passive"))
      (node (ref "J11") (pin "5") (pinfunction "5_5") (pintype "passive"))
      (node (ref "J11") (pin "6") (pinfunction "6_6") (pintype "passive"))
      (node (ref "J12") (pin "4") (pinfunction "4_4") (pintype "passive"))
      (node (ref "J12") (pin "5") (pinfunction "5_5") (pintype "passive"))
      (node (ref "J12") (pin "6") (pinfunction "6_6") (pintype "passive"))
      (node (ref "J13") (pin "1") (pinfunction "1_1") (pintype "passive"))
      (node (ref "J14") (pin "1") (pinfunction "1_1") (pintype "passive"))
      (node (ref "J15") (pin "1") (pinfunction "1_1") (pintype "passive"))
      (node (ref "J16") (pin "1") (pinfunction "1_1") (pintype "passive"))
      (node (ref "J17") (pin "1") (pinfunction "1_1") (pintype "passive"))
      (node (ref "J18") (pin "1") (pinfunction "1_1") (pintype "passive"))
      (node (ref "J19") (pin "1") (pinfunction "1_1") (pintype "passive"))
      (node (ref "J2") (pin "5") (pinfunction "5_5") (pintype "passive"))
      (node (ref "J2") (pin "6") (pinfunction "6_6") (pintype "passive"))
      (node (ref "J2") (pin "7") (pinfunction "7_7") (pintype "passive"))
      (node (ref "J2") (pin "8") (pinfunction "8_8") (pintype "passive"))
      (node (ref "J2") (pin "9") (pinfunction "9_9") (pintype "passive"))
      (node (ref "J20") (pin "1") (pinfunction "1_1") (pintype "passive"))
      (node (ref "J21") (pin "1") (pinfunction "1_1") (pintype "passive"))
      (node (ref "J22") (pin "1") (pinfunction "1_1") (pintype "passive"))
      (node (ref "J23") (pin "1") (pinfunction "1_1") (pintype "passive"))
      (node (ref "J24") (pin "1") (pinfunction "1_1") (pintype "passive"))
      (node (ref "J3") (pin "2") (pinfunction "2_2") (pintype "passive"))
      (node (ref "J4") (pin "4") (pinfunction "4_4") (pintype "passive"))
      (node (ref "J4") (pin "5") (pinfunction "5_5") (pintype "passive"))
      (node (ref "J4") (pin "6") (pinfunction "6_6") (pintype "passive"))
      (node (ref "J5") (pin "4") (pinfunction "4_4") (pintype "passive"))
      (node (ref "J5") (pin "5") (pinfunction "5_5") (pintype "passive"))
      (node (ref "J5") (pin "6") (pinfunction "6_6") (pintype "passive"))
      (node (ref "J6") (pin "4") (pinfunction "4_4") (pintype "passive"))
      (node (ref "J6") (pin "5") (pinfunction "5_5") (pintype "passive"))
      (node (ref "J6") (pin "6") (pinfunction "6_6") (pintype "passive"))
      (node (ref "J7") (pin "4") (pinfunction "4_4") (pintype "passive"))
      (node (ref "J7") (pin "5") (pinfunction "5_5") (pintype "passive"))
      (node (ref "J7") (pin "6") (pinfunction "6_6") (pintype "passive"))
      (node (ref "J8") (pin "4") (pinfunction "4_4") (pintype "passive"))
      (node (ref "J8") (pin "5") (pinfunction "5_5") (pintype "passive"))
      (node (ref "J8") (pin "6") (pinfunction "6_6") (pintype "passive"))
      (node (ref "J9") (pin "1") (pinfunction "1_1") (pintype "passive"))
      (node (ref "Q51") (pin "2") (pinfunction "S_2") (pintype "passive"))
      (node (ref "R17") (pin "2") (pinfunction "2_2") (pintype "passive"))
      (node (ref "R22") (pin "2") (pinfunction "2_2") (pintype "passive"))
      (node (ref "R24") (pin "2") (pinfunction "2_2") (pintype "passive"))
      (node (ref "R28") (pin "2") (pinfunction "2_2") (pintype "passive"))
      (node (ref "R29") (pin "2") (pinfunction "2_2") (pintype "passive"))
      (node (ref "R5") (pin "1") (pinfunction "1_1") (pintype "passive"))
      (node (ref "R8") (pin "2") (pinfunction "2_2") (pintype "passive"))
      (node (ref "U10") (pin "20") (pinfunction "AVSS_20") (pintype "passive"))
      (node (ref "U10") (pin "25") (pinfunction "VSS_25") (pintype "passive"))
      (node (ref "U10") (pin "41") (pinfunction "VSS_41") (pintype "passive"))
      (node (ref "U10") (pin "9") (pinfunction "VSS_9") (pintype "passive"))
      (node (ref "U27") (pin "4") (pinfunction "GND_4") (pintype "passive"))
      (node (ref "U28") (pin "2") (pinfunction "GND_2") (pintype "passive"))
      (node (ref "U28") (pin "3") (pinfunction "GND_3") (pintype "passive"))
      (node (ref "U28") (pin "4") (pinfunction "N.C._4") (pintype "passive"))
      (node (ref "U28") (pin "5") (pinfunction "N.C._5") (pintype "passive"))
      (node (ref "U28") (pin "6") (pinfunction "GND_6") (pintype "passive"))
      (node (ref "U28") (pin "7") (pinfunction "GND_7") (pintype "passive"))
      (node (ref "U29") (pin "6") (pinfunction "GND_6") (pintype "passive"))
      (node (ref "U29") (pin "7") (pinfunction "GND_7") (pintype "passive"))
      (node (ref "U34") (pin "4") (pinfunction "GND_4") (pintype "passive"))
      (node (ref "U5") (pin "2") (pinfunction "GND_2") (pintype "passive"))
      (node (ref "U6") (pin "6") (pinfunction "GND_6") (pintype "passive"))
      (node (ref "U6") (pin "7") (pinfunction "GND_7") (pintype "passive"))
      (node (ref "U7") (pin "4") (pinfunction "GND_4") (pintype "passive"))
      (node (ref "U8") (pin "4") (pinfunction "GND_4") (pintype "passive"))
      (node (ref "U9") (pin "6") (pinfunction "GND_6") (pintype "passive"))
      (node (ref "U9") (pin "7") (pinfunction "GND_7") (pintype "passive"))
    )
    (net (code "45") (name "Net-(U9-ADJ)") (class "Default")
      (node (ref "R16") (pin "2") (pinfunction "2_2") (pintype "passive"))
      (node (ref "R17") (pin "1") (pinfunction "1_1") (pintype "passive"))
      (node (ref "U9") (pin "2") (pinfunction "ADJ_2") (pintype "passive"))
    )
    (net (code "46") (name "Net-(U10-AN2{slash}C2IN2-{slash}VMIO{slash}RPI34{slash}RB2)") (class "Default")
      (node (ref "TP7") (pin "1") (pinfunction "1_1") (pintype "passive"))
      (node (ref "U10") (pin "14") (pinfunction "AN2/C2IN2-/VMIO/RPI34/RB2_14") (pintype "passive"))
    )
    (net (code "47") (name "Net-(U10-AN3{slash}C2IN1+{slash}VPIO{slash}RPI35{slash}RB3)") (class "Default")
      (node (ref "TP6") (pin "1") (pinfunction "1_1") (pintype "passive"))
      (node (ref "U10") (pin "13") (pinfunction "AN3/C2IN1+/VPIO/RPI35/RB3_13") (pintype "passive"))
    )
    (net (code "48") (name "Net-(U10-AN4{slash}C1IN2-{slash}USBOEN{slash}RPI36{slash}RB4)") (class "Default")
      (node (ref "TP5") (pin "1") (pinfunction "1_1") (pintype "passive"))
      (node (ref "U10") (pin "12") (pinfunction "AN4/C1IN2-/USBOEN/RPI36/RB4_12") (pintype "passive"))
    )
    (net (code "49") (name "Net-(U10-AN5{slash}C1IN1+{slash}VBUSON{slash}VBUSST{slash}RPI37{slash}RB5)") (class "Default")
      (node (ref "TP3") (pin "1") (pinfunction "1_1") (pintype "passive"))
      (node (ref "U10") (pin "11") (pinfunction "AN5/C1IN1+/VBUSON/VBUSST/RPI37/RB5_11") (pintype "passive"))
    )
    (net (code "50") (name "Net-(U10-AN8{slash}PMA6{slash}RPI40{slash}RB8)") (class "Default")
      (node (ref "TP10") (pin "1") (pinfunction "1_1") (pintype "passive"))
      (node (ref "U10") (pin "21") (pinfunction "AN8/PMA6/RPI40/RB8_21") (pintype "passive"))
    )
    (net (code "51") (name "Net-(U10-AN9{slash}PMA7{slash}{slash}RPI41{slash}RB9)") (class "Default")
      (node (ref "TP11") (pin "1") (pinfunction "1_1") (pintype "passive"))
      (node (ref "U10") (pin "22") (pinfunction "AN9/PMA7//RPI41/RB9_22") (pintype "passive"))
    )
    (net (code "52") (name "Net-(U10-AN14{slash}PMA1{slash}RPI46{slash}RB14)") (class "Default")
      (node (ref "TP124") (pin "1") (pinfunction "1_1") (pintype "passive"))
      (node (ref "U10") (pin "29") (pinfunction "AN14/PMA1/RPI46/RB14_29") (pintype "passive"))
    )
    (net (code "53") (name "Net-(U10-AN15{slash}PMA0{slash}RPI47{slash}RB15)") (class "Default")
      (node (ref "TP125") (pin "1") (pinfunction "1_1") (pintype "passive"))
      (node (ref "U10") (pin "30") (pinfunction "AN15/PMA0/RPI47/RB15_30") (pintype "passive"))
    )
    (net (code "54") (name "Net-(U10-ASDA1{slash}DPLN{slash}RPI73{slash}RD9)") (class "Default")
      (node (ref "TP12") (pin "1") (pinfunction "1_1") (pintype "passive"))
      (node (ref "U10") (pin "43") (pinfunction "ASDA1/DPLN/RPI73/RD9_43") (pintype "passive"))
    )
    (net (code "55") (name "Net-(U10-C3IN1+{slash}VCMPST3{slash}RP71{slash}RD7)") (class "Default")
      (node (ref "TP18") (pin "1") (pinfunction "1_1") (pintype "passive"))
      (node (ref "U10") (pin "55") (pinfunction "C3IN1+/VCMPST3/RP71/RD7_55") (pintype "passive"))
    )
    (net (code "56") (name "Net-(U10-C3IN2-{slash}RP70{slash}RD6)") (class "Default")
      (node (ref "TP19") (pin "1") (pinfunction "1_1") (pintype "passive"))
      (node (ref "U10") (pin "54") (pinfunction "C3IN2-/RP70/RD6_54") (pintype "passive"))
    )
    (net (code "57") (name "Net-(U10-DPH{slash}RP66{slash}RD2)") (class "Default")
      (node (ref "TP22") (pin "1") (pinfunction "1_1") (pintype "passive"))
      (node (ref "U10") (pin "50") (pinfunction "DPH/RP66/RD2_50") (pintype "passive"))
    )
    (net (code "58") (name "Net-(U10-INT0{slash}DMH{slash}RP64{slash}RD0)") (class "Default")
      (node (ref "TP24") (pin "1") (pinfunction "1_1") (pintype "passive"))
      (node (ref "U10") (pin "46") (pinfunction "INT0/DMH/RP64/RD0_46") (pintype "passive"))
    )
    (net (code "59") (name "Net-(U10-PMBE{slash}RP67{slash}RD3)") (class "Default")
      (node (ref "TP20") (pin "1") (pinfunction "1_1") (pintype "passive"))
      (node (ref "U10") (pin "51") (pinfunction "PMBE/RP67/RD3_51") (pintype "passive"))
    )
    (net (code "60") (name "Net-(U10-PMRD{slash}RP69{slash}RD5)") (class "Default")
      (node (ref "TP25") (pin "1") (pinfunction "1_1") (pintype "passive"))
      (node (ref "U10") (pin "53") (pinfunction "PMRD/RP69/RD5_53") (pintype "passive"))
    )
    (net (code "61") (name "Net-(U10-RTCC{slash}DMLN{slash}RPI72{slash}RD8)") (class "Default")
      (node (ref "TP13") (pin "1") (pinfunction "1_1") (pintype "passive"))
      (node (ref "U10") (pin "42") (pinfunction "RTCC/DMLN/RPI72/RD8_42") (pintype "passive"))
    )
    (net (code "62") (name "Net-(U10-SCL2{slash}PMA8{slash}RP101{slash}RF5)") (class "Default")
      (node (ref "TP127") (pin "1") (pinfunction "1_1") (pintype "passive"))
      (node (ref "U10") (pin "32") (pinfunction "SCL2/PMA8/RP101/RF5_32") (pintype "passive"))
    )
    (net (code "63") (name "Net-(U10-SDA2{slash}PMA9{slash}RP100{slash}RF4)") (class "Default")
      (node (ref "TP126") (pin "1") (pinfunction "1_1") (pintype "passive"))
      (node (ref "U10") (pin "31") (pinfunction "SDA2/PMA9/RP100/RF4_31") (pintype "passive"))
    )
    (net (code "64") (name "Net-(U10-TCK{slash}AN12{slash}PMA11{slash}RPI44{slash}RB12)") (class "Default")
      (node (ref "TP2") (pin "1") (pinfunction "1_1") (pintype "passive"))
      (node (ref "U10") (pin "27") (pinfunction "TCK/AN12/PMA11/RPI44/RB12_27") (pintype "passive"))
    )
    (net (code "65") (name "Net-(U10-TDI{slash}AN13{slash}PMA10{slash}RPI45{slash}RB13)") (class "Default")
      (node (ref "TP123") (pin "1") (pinfunction "1_1") (pintype "passive"))
      (node (ref "U10") (pin "28") (pinfunction "TDI/AN13/PMA10/RPI45/RB13_28") (pintype "passive"))
    )
    (net (code "66") (name "Net-(U10-TDO{slash}AN11{slash}PMA12{slash}RPI43{slash}RB11)") (class "Default")
      (node (ref "TP132") (pin "1") (pinfunction "1_1") (pintype "passive"))
      (node (ref "U10") (pin "24") (pinfunction "TDO/AN11/PMA12/RPI43/RB11_24") (pintype "passive"))
    )
    (net (code "67") (name "Net-(U10-TMS{slash}AN10{slash}CVREF{slash}PMA13{slash}RPI42{slash}RB10)") (class "Default")
      (node (ref "TP131") (pin "1") (pinfunction "1_1") (pintype "passive"))
      (node (ref "U10") (pin "23") (pinfunction "TMS/AN10/CVREF/PMA13/RPI42/RB10_23") (pintype "passive"))
    )
    (net (code "68") (name "Net-(U10-USBID{slash}RP99{slash}RF3)") (class "Default")
      (node (ref "TP21") (pin "1") (pinfunction "1_1") (pintype "passive"))
      (node (ref "U10") (pin "33") (pinfunction "USBID/RP99/RF3_33") (pintype "passive"))
    )
    (net (code "69") (name "Net-(U10-VCMPST1{slash}RP96{slash}RF0)") (class "Default")
      (node (ref "TP129") (pin "1") (pinfunction "1_1") (pintype "passive"))
      (node (ref "U10") (pin "58") (pinfunction "VCMPST1/RP96/RF0_58") (pintype "passive"))
    )
    (net (code "70") (name "Net-(U10-VCMPST2{slash}RP97{slash}RF1)") (class "Default")
      (node (ref "TP128") (pin "1") (pinfunction "1_1") (pintype "passive"))
      (node (ref "U10") (pin "59") (pinfunction "VCMPST2/RP97/RF1_59") (pintype "passive"))
    )
    (net (code "71") (name "Net-(U10-VCPCON{slash}RP65{slash}RD1)") (class "Default")
      (node (ref "TP23") (pin "1") (pinfunction "1_1") (pintype "passive"))
      (node (ref "U10") (pin "49") (pinfunction "VCPCON/RP65/RD1_49") (pintype "passive"))
    )
    (net (code "72") (name "Net-(U29-ADJ)") (class "Default")
      (node (ref "R27") (pin "2") (pinfunction "2_2") (pintype "passive"))
      (node (ref "R28") (pin "1") (pinfunction "1_1") (pintype "passive"))
      (node (ref "U29") (pin "2") (pinfunction "ADJ_2") (pintype "passive"))
    )
    (net (code "73") (name "unconnected-(J2-Pad4)") (class "Default")
      (node (ref "J2") (pin "4") (pinfunction "4_4") (pintype "passive+no_connect"))
    )
    (net (code "74") (name "unconnected-(U5-N.C.-Pad4)") (class "Default")
      (node (ref "U5") (pin "4") (pinfunction "N.C._4") (pintype "passive+no_connect"))
    )
    (net (code "75") (name "unconnected-(U6-NC-Pad2)") (class "Default")
      (node (ref "U6") (pin "2") (pinfunction "NC_2") (pintype "passive+no_connect"))
    )
    (net (code "76") (name "unconnected-(U6-NC-Pad3)") (class "Default")
      (node (ref "U6") (pin "3") (pinfunction "NC_3") (pintype "passive+no_connect"))
    )
    (net (code "77") (name "unconnected-(U6-NC-Pad4)") (class "Default")
      (node (ref "U6") (pin "4") (pinfunction "NC_4") (pintype "passive+no_connect"))
    )
    (net (code "78") (name "unconnected-(U9-NC-Pad3)") (class "Default")
      (node (ref "U9") (pin "3") (pinfunction "NC_3") (pintype "passive+no_connect"))
    )
    (net (code "79") (name "unconnected-(U9-NC-Pad4)") (class "Default")
      (node (ref "U9") (pin "4") (pinfunction "NC_4") (pintype "passive+no_connect"))
    )
    (net (code "80") (name "unconnected-(U29-NC-Pad3)") (class "Default")
      (node (ref "U29") (pin "3") (pinfunction "NC_3") (pintype "passive+no_connect"))
    )
    (net (code "81") (name "unconnected-(U29-NC-Pad4)") (class "Default")
      (node (ref "U29") (pin "4") (pinfunction "NC_4") (pintype "passive+no_connect"))
    )
  )
)
